# SCH.net
KiCad netlist of a schematic drawn in Altium Designer
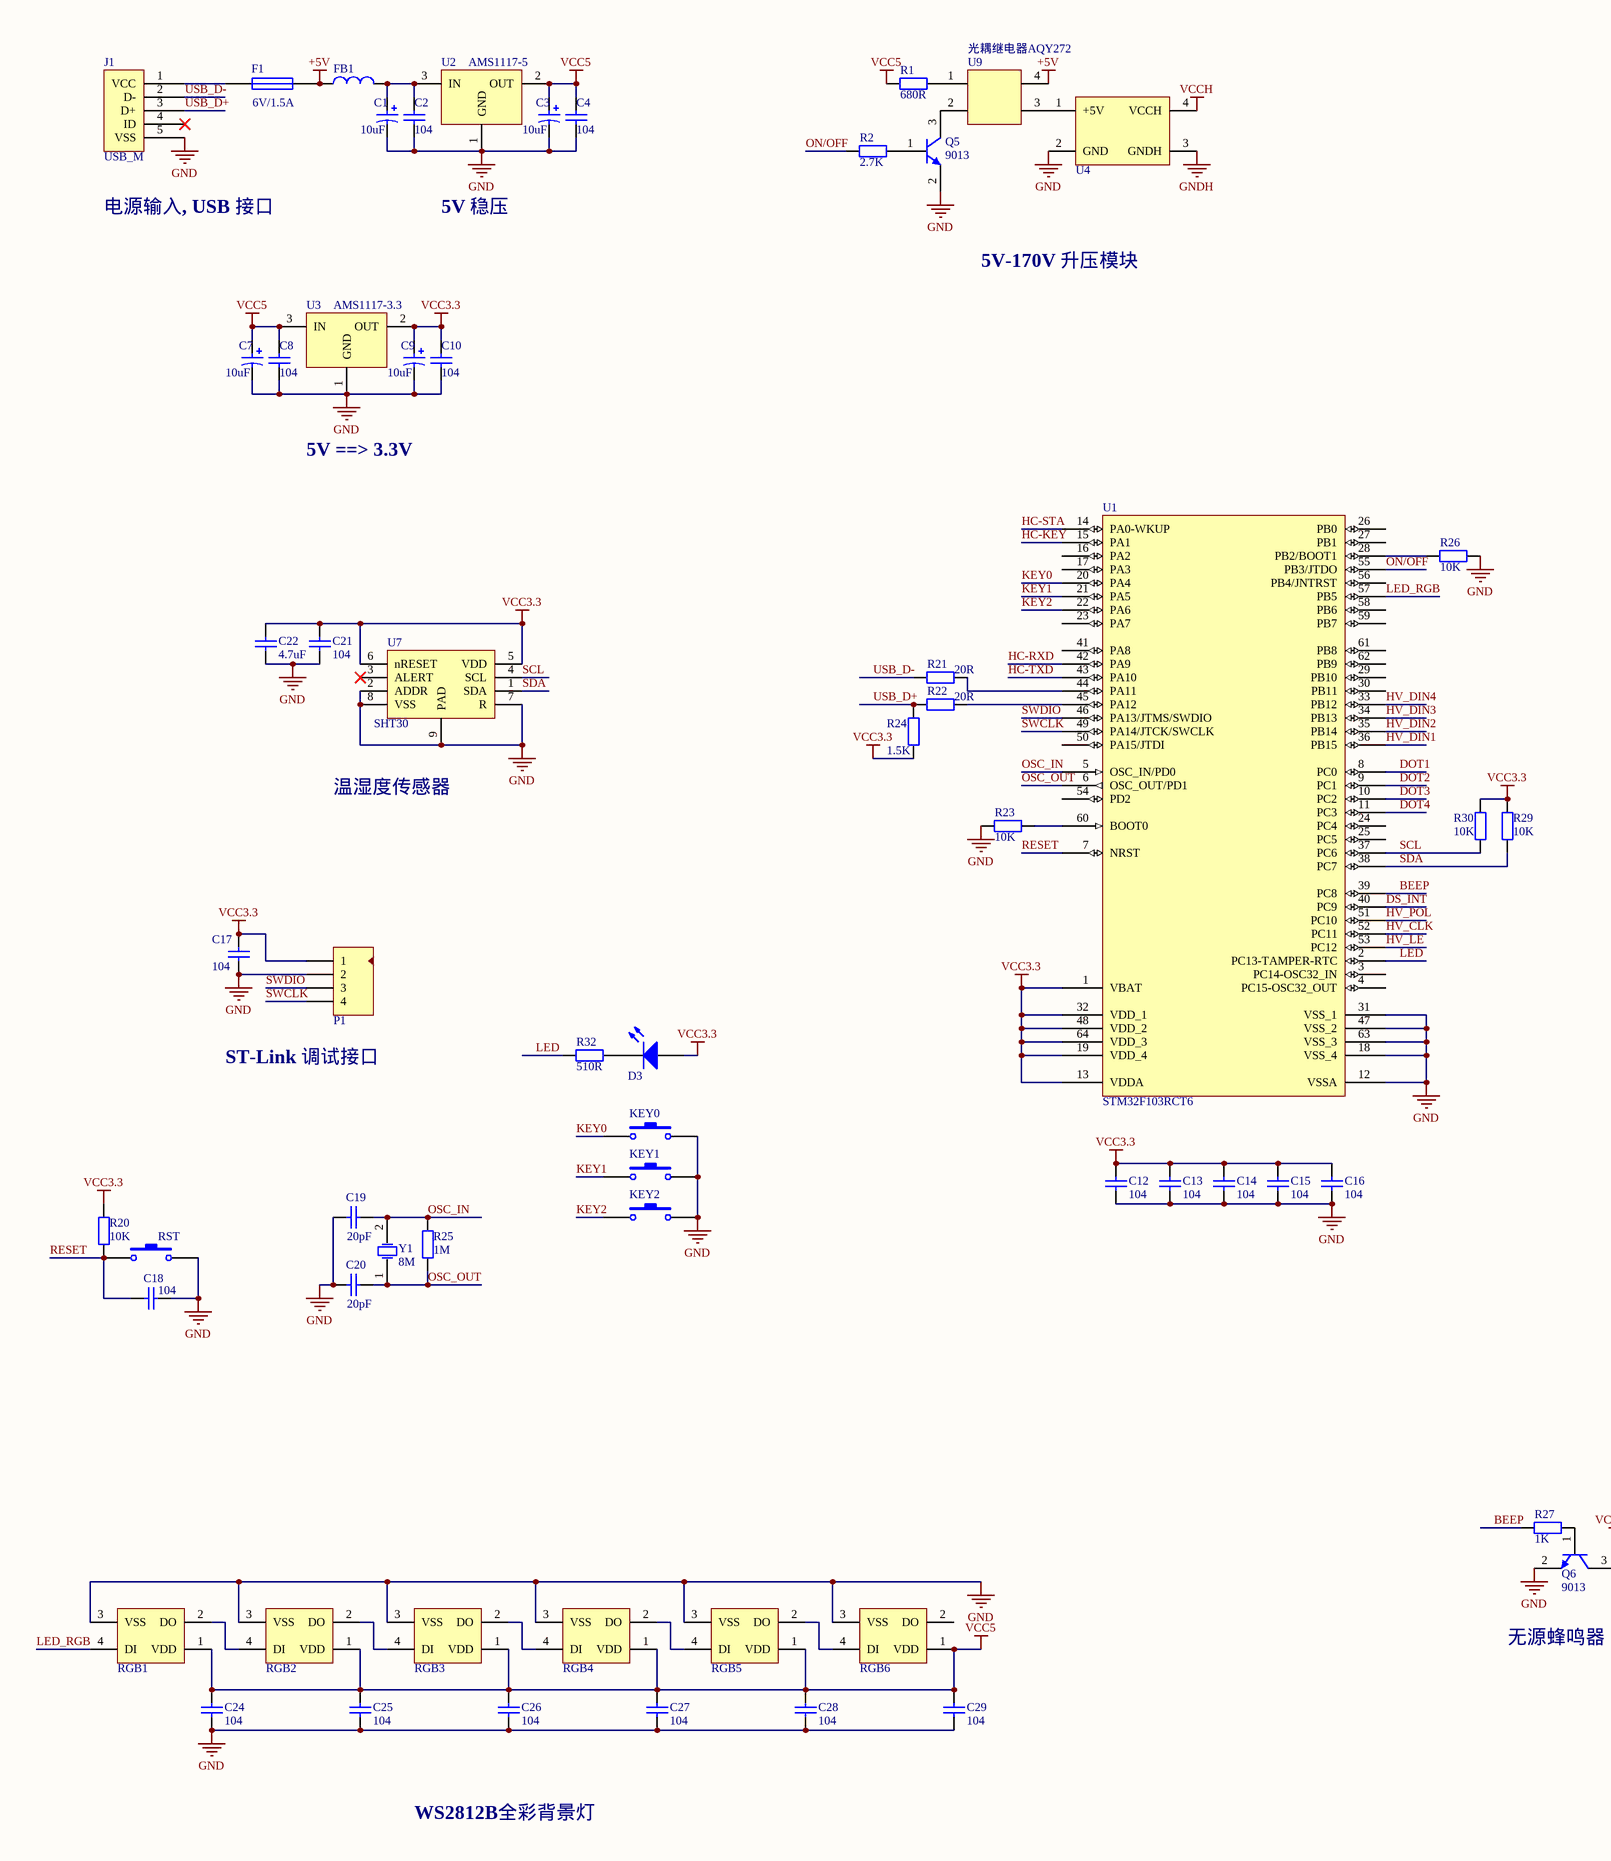
[diagram p0: SCH.SchDoc, left]
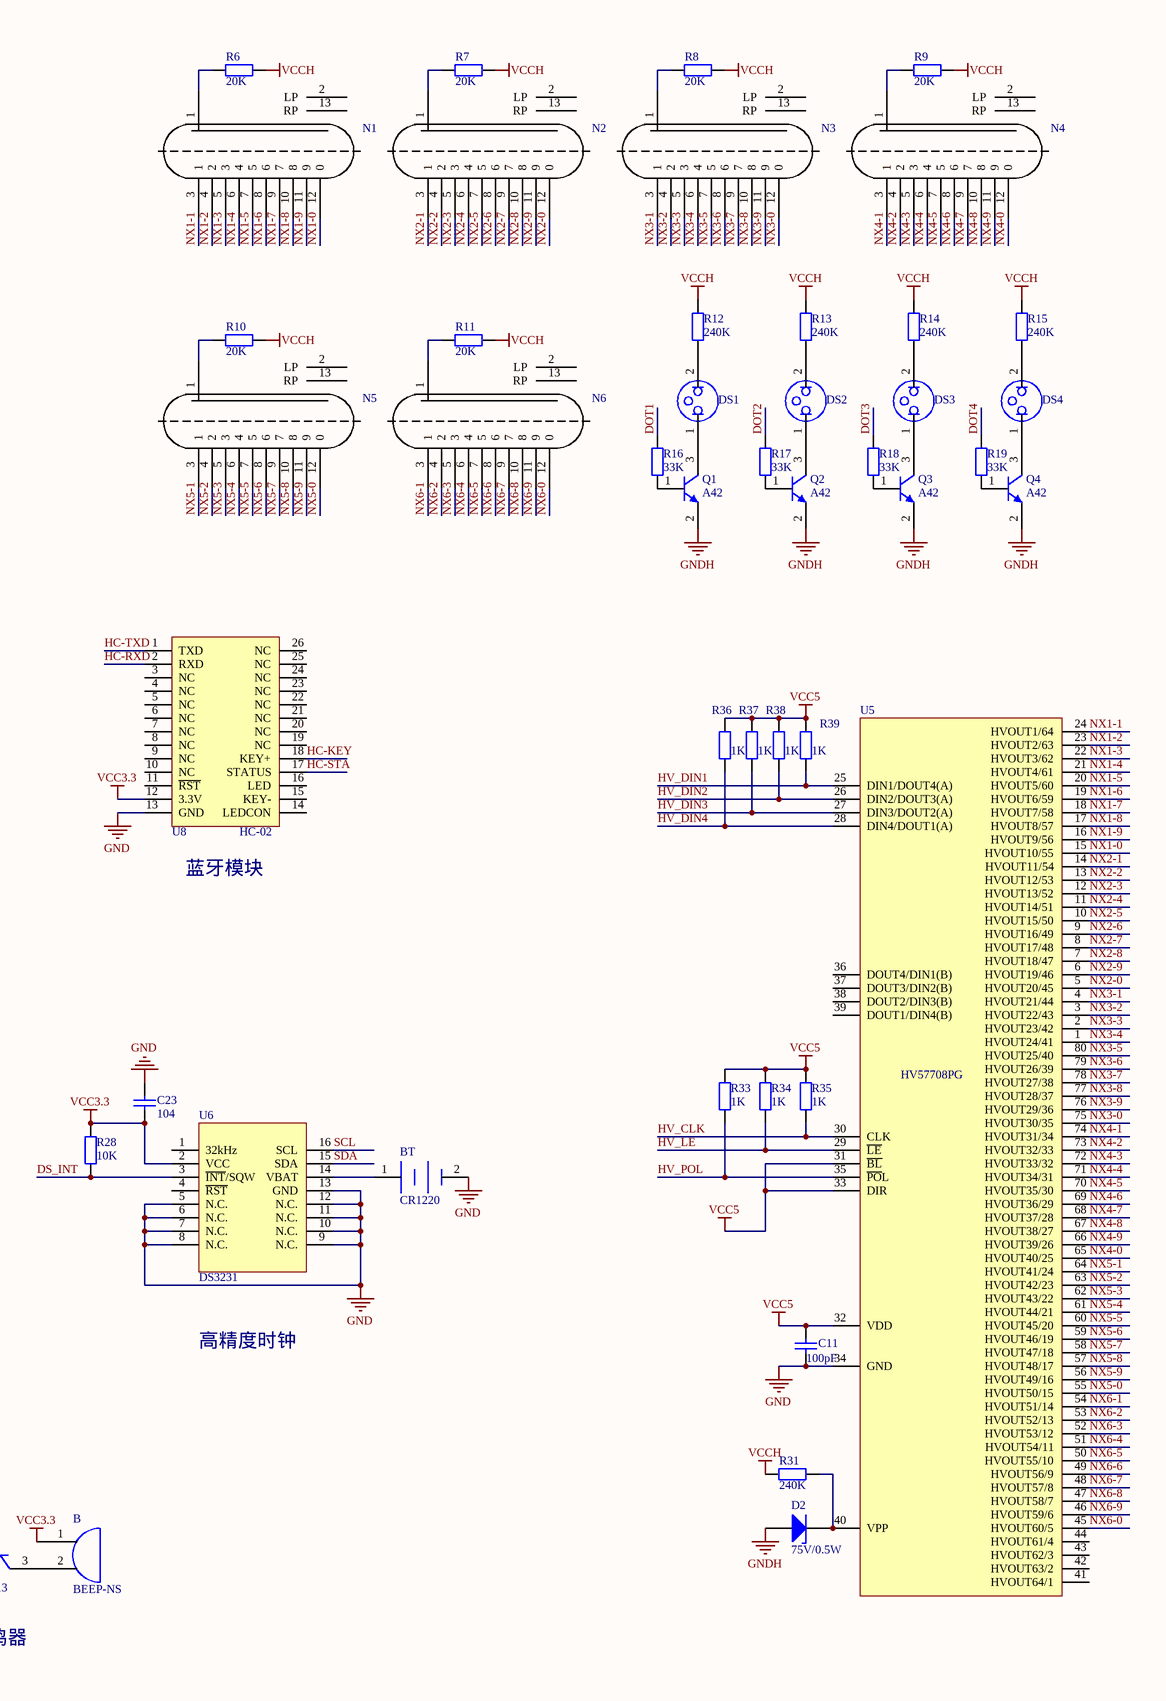
[diagram p1: SCH.SchDoc, right]

(export (version "E")
  (design (tool "Eeschema 10.0.6"))
  (components
    (comp (ref "B")
      (value "BEEP-NS")
      (footprint "BEEP-NS")
      (description "无源蜂鸣器")
      (libsource (lib "ChunLee") (part "BEEP-NS"))
    )
    (comp (ref "BT")
      (value "Battery")
      (footprint "CR1220")
      (fields (field (name "TYPE") "CR1220"))
      (libsource (lib "ChunLee") (part "Battery"))
    )
    (comp (ref "C1")
      (value "10uF")
      (footprint "C-1210")
      (description "钽电容")
      (fields (field (name "Comment") "Cap-Pol") (field (name "PUBLISHER") "Altium Limited"))
      (libsource (lib "ChunLee") (part "Cap-Pol-A"))
    )
    (comp (ref "C2")
      (value "104")
      (footprint "C-0805")
      (description "贴片瓷片电容")
      (fields (field (name "Comment") "Cap-S") (field (name "PUBLISHER") "Altium Limited"))
      (libsource (lib "ChunLee") (part "Cap-S"))
    )
    (comp (ref "C3")
      (value "10uF")
      (footprint "C-1210")
      (description "钽电容")
      (fields (field (name "Comment") "Cap-Pol") (field (name "PUBLISHER") "Altium Limited"))
      (libsource (lib "ChunLee") (part "Cap-Pol-A"))
    )
    (comp (ref "C4")
      (value "104")
      (footprint "C-0805")
      (description "贴片瓷片电容")
      (fields (field (name "Comment") "Cap-S") (field (name "PUBLISHER") "Altium Limited"))
      (libsource (lib "ChunLee") (part "Cap-S"))
    )
    (comp (ref "C7")
      (value "10uF")
      (footprint "C-1210")
      (description "钽电容")
      (fields (field (name "Comment") "Cap-Pol") (field (name "PUBLISHER") "Altium Limited"))
      (libsource (lib "ChunLee") (part "Cap-Pol-A"))
    )
    (comp (ref "C8")
      (value "104")
      (footprint "C-0805")
      (description "贴片瓷片电容")
      (fields (field (name "Comment") "Cap-S") (field (name "PUBLISHER") "Altium Limited"))
      (libsource (lib "ChunLee") (part "Cap-S"))
    )
    (comp (ref "C9")
      (value "10uF")
      (footprint "C-1210")
      (description "钽电容")
      (fields (field (name "Comment") "Cap-Pol") (field (name "PUBLISHER") "Altium Limited"))
      (libsource (lib "ChunLee") (part "Cap-Pol-A"))
    )
    (comp (ref "C10")
      (value "104")
      (footprint "C-0805")
      (description "贴片瓷片电容")
      (fields (field (name "Comment") "Cap-S") (field (name "PUBLISHER") "Altium Limited"))
      (libsource (lib "ChunLee") (part "Cap-S"))
    )
    (comp (ref "C11")
      (value "100pF")
      (footprint "C-0805")
      (description "贴片瓷片电容")
      (fields (field (name "Comment") "Cap-S") (field (name "PUBLISHER") "Altium Limited"))
      (libsource (lib "ChunLee") (part "Cap-S"))
    )
    (comp (ref "C12")
      (value "104")
      (footprint "C-0805")
      (description "贴片瓷片电容")
      (fields (field (name "Comment") "Cap-S") (field (name "PUBLISHER") "Altium Limited"))
      (libsource (lib "ChunLee") (part "Cap-S"))
    )
    (comp (ref "C13")
      (value "104")
      (footprint "C-0805")
      (description "贴片瓷片电容")
      (fields (field (name "Comment") "Cap-S") (field (name "PUBLISHER") "Altium Limited"))
      (libsource (lib "ChunLee") (part "Cap-S"))
    )
    (comp (ref "C14")
      (value "104")
      (footprint "C-0805")
      (description "贴片瓷片电容")
      (fields (field (name "Comment") "Cap-S") (field (name "PUBLISHER") "Altium Limited"))
      (libsource (lib "ChunLee") (part "Cap-S"))
    )
    (comp (ref "C15")
      (value "104")
      (footprint "C-0805")
      (description "贴片瓷片电容")
      (fields (field (name "Comment") "Cap-S") (field (name "PUBLISHER") "Altium Limited"))
      (libsource (lib "ChunLee") (part "Cap-S"))
    )
    (comp (ref "C16")
      (value "104")
      (footprint "C-0805")
      (description "贴片瓷片电容")
      (fields (field (name "Comment") "Cap-S") (field (name "PUBLISHER") "Altium Limited"))
      (libsource (lib "ChunLee") (part "Cap-S"))
    )
    (comp (ref "C17")
      (value "104")
      (footprint "C-0805")
      (description "贴片瓷片电容")
      (fields (field (name "Comment") "Cap-S") (field (name "PUBLISHER") "Altium Limited"))
      (libsource (lib "ChunLee") (part "Cap-S"))
    )
    (comp (ref "C18")
      (value "104")
      (footprint "C-0805")
      (description "贴片瓷片电容")
      (fields (field (name "Comment") "Cap-S") (field (name "PUBLISHER") "Altium Limited"))
      (libsource (lib "ChunLee") (part "Cap-S"))
    )
    (comp (ref "C19")
      (value "20pF")
      (footprint "C-0805")
      (description "贴片瓷片电容")
      (fields (field (name "Comment") "Cap-S") (field (name "PUBLISHER") "Altium Limited"))
      (libsource (lib "ChunLee") (part "Cap-S"))
    )
    (comp (ref "C20")
      (value "20pF")
      (footprint "C-0805")
      (description "贴片瓷片电容")
      (fields (field (name "Comment") "Cap-S") (field (name "PUBLISHER") "Altium Limited"))
      (libsource (lib "ChunLee") (part "Cap-S"))
    )
    (comp (ref "C21")
      (value "104")
      (footprint "C-0805")
      (description "贴片瓷片电容")
      (fields (field (name "Comment") "Cap-S") (field (name "PUBLISHER") "Altium Limited"))
      (libsource (lib "ChunLee") (part "Cap-S"))
    )
    (comp (ref "C22")
      (value "4.7uF")
      (footprint "C-0805")
      (description "贴片瓷片电容")
      (fields (field (name "Comment") "Cap-S") (field (name "PUBLISHER") "Altium Limited"))
      (libsource (lib "ChunLee") (part "Cap-S"))
    )
    (comp (ref "C23")
      (value "104")
      (footprint "C-0805")
      (description "贴片瓷片电容")
      (fields (field (name "Comment") "Cap-S") (field (name "PUBLISHER") "Altium Limited"))
      (libsource (lib "ChunLee") (part "Cap-S"))
    )
    (comp (ref "C24")
      (value "104")
      (footprint "C-0805")
      (description "贴片瓷片电容")
      (fields (field (name "Comment") "Cap-S") (field (name "PUBLISHER") "Altium Limited"))
      (libsource (lib "ChunLee") (part "Cap-S"))
    )
    (comp (ref "C25")
      (value "104")
      (footprint "C-0805")
      (description "贴片瓷片电容")
      (fields (field (name "Comment") "Cap-S") (field (name "PUBLISHER") "Altium Limited"))
      (libsource (lib "ChunLee") (part "Cap-S"))
    )
    (comp (ref "C26")
      (value "104")
      (footprint "C-0805")
      (description "贴片瓷片电容")
      (fields (field (name "Comment") "Cap-S") (field (name "PUBLISHER") "Altium Limited"))
      (libsource (lib "ChunLee") (part "Cap-S"))
    )
    (comp (ref "C27")
      (value "104")
      (footprint "C-0805")
      (description "贴片瓷片电容")
      (fields (field (name "Comment") "Cap-S") (field (name "PUBLISHER") "Altium Limited"))
      (libsource (lib "ChunLee") (part "Cap-S"))
    )
    (comp (ref "C28")
      (value "104")
      (footprint "C-0805")
      (description "贴片瓷片电容")
      (fields (field (name "Comment") "Cap-S") (field (name "PUBLISHER") "Altium Limited"))
      (libsource (lib "ChunLee") (part "Cap-S"))
    )
    (comp (ref "C29")
      (value "104")
      (footprint "C-0805")
      (description "贴片瓷片电容")
      (fields (field (name "Comment") "Cap-S") (field (name "PUBLISHER") "Altium Limited"))
      (libsource (lib "ChunLee") (part "Cap-S"))
    )
    (comp (ref "D2")
      (value "75V/0.5W")
      (footprint "D-ll34")
      (description "稳压二极管")
      (fields (field (name "Comment") "ZMM75") (field (name "PUBLISHER") "Altium Limited"))
      (libsource (lib "ChunLee") (part "Diode-Z"))
    )
    (comp (ref "D3")
      (value "LED0")
      (footprint "LED-0805")
      (description "发光二极管")
      (fields (field (name "PUBLISHER") "Altium Limited"))
      (libsource (lib "ChunLee") (part "LED0"))
    )
    (comp (ref "DS1")
      (value "Neon")
      (footprint "PIN2")
      (description "氖泡")
      (libsource (lib "ChunLee") (part "Neon_Lamp"))
    )
    (comp (ref "DS2")
      (value "Neon")
      (footprint "PIN2")
      (description "氖泡")
      (libsource (lib "ChunLee") (part "Neon_Lamp"))
    )
    (comp (ref "DS3")
      (value "Neon")
      (footprint "PIN2")
      (description "氖泡")
      (libsource (lib "ChunLee") (part "Neon_Lamp"))
    )
    (comp (ref "DS4")
      (value "Neon")
      (footprint "PIN2")
      (description "氖泡")
      (libsource (lib "ChunLee") (part "Neon_Lamp"))
    )
    (comp (ref "F1")
      (value "6V/1.5A")
      (footprint "1206")
      (description "保险丝")
      (fields (field (name "Comment") "Fuse1"))
      (libsource (lib "ChunLee") (part "Fuse1"))
    )
    (comp (ref "FB1")
      (value "Inductor")
      (footprint "0805-1")
      (description "磁珠")
      (fields (field (name "PUBLISHER") "Altium Limited"))
      (libsource (lib "ChunLee") (part "Inductor"))
    )
    (comp (ref "J1")
      (value "USB_M")
      (footprint "USB_MICRO")
      (description "Micro/Mini USB")
      (libsource (lib "HDR_ChunLee") (part "USB_M"))
    )
    (comp (ref "KEY0")
      (value "KEY")
      (footprint "SW_PB2_C1")
      (description "微动开关")
      (fields (field (name "PUBLISHER") "Altium Limited"))
      (libsource (lib "ChunLee") (part "SW-PB"))
    )
    (comp (ref "KEY1")
      (value "KEY")
      (footprint "SW_PB2_C1")
      (description "微动开关")
      (fields (field (name "PUBLISHER") "Altium Limited"))
      (libsource (lib "ChunLee") (part "SW-PB"))
    )
    (comp (ref "KEY2")
      (value "KEY")
      (footprint "SW_PB2_C1")
      (description "微动开关")
      (fields (field (name "PUBLISHER") "Altium Limited"))
      (libsource (lib "ChunLee") (part "SW-PB"))
    )
    (comp (ref "N1")
      (value "IN_14")
      (footprint "IN_14")
      (description "辉光管")
      (libsource (lib "ChunLee") (part "IN_14"))
    )
    (comp (ref "N2")
      (value "IN_14")
      (footprint "IN_14")
      (description "辉光管")
      (libsource (lib "ChunLee") (part "IN_14"))
    )
    (comp (ref "N3")
      (value "IN_14")
      (footprint "IN_14")
      (description "辉光管")
      (libsource (lib "ChunLee") (part "IN_14"))
    )
    (comp (ref "N4")
      (value "IN_14")
      (footprint "IN_14")
      (description "辉光管")
      (libsource (lib "ChunLee") (part "IN_14"))
    )
    (comp (ref "N5")
      (value "IN_14")
      (footprint "IN_14")
      (description "辉光管")
      (libsource (lib "ChunLee") (part "IN_14"))
    )
    (comp (ref "N6")
      (value "IN_14")
      (footprint "IN_14")
      (description "辉光管")
      (libsource (lib "ChunLee") (part "IN_14"))
    )
    (comp (ref "P1")
      (value "Header 4")
      (footprint "HDR4X1-2.54")
      (description "接插件")
      (fields (field (name "PUBLISHER") "Altium Limited"))
      (libsource (lib "HDR_ChunLee") (part "Header 4"))
    )
    (comp (ref "Q1")
      (value "A42")
      (footprint "SOT23-3")
      (description "贴片三极管")
      (fields (field (name "PUBLISHER") "Altium Limited"))
      (libsource (lib "ChunLee") (part "NPN1"))
    )
    (comp (ref "Q2")
      (value "A42")
      (footprint "SOT23-3")
      (description "贴片三极管")
      (fields (field (name "PUBLISHER") "Altium Limited"))
      (libsource (lib "ChunLee") (part "NPN1"))
    )
    (comp (ref "Q3")
      (value "A42")
      (footprint "SOT23-3")
      (description "贴片三极管")
      (fields (field (name "PUBLISHER") "Altium Limited"))
      (libsource (lib "ChunLee") (part "NPN1"))
    )
    (comp (ref "Q4")
      (value "A42")
      (footprint "SOT23-3")
      (description "贴片三极管")
      (fields (field (name "PUBLISHER") "Altium Limited"))
      (libsource (lib "ChunLee") (part "NPN1"))
    )
    (comp (ref "Q5")
      (value "9013")
      (footprint "SOT23-3")
      (description "贴片三极管")
      (fields (field (name "PUBLISHER") "Altium Limited"))
      (libsource (lib "ChunLee") (part "NPN1"))
    )
    (comp (ref "Q6")
      (value "9013")
      (footprint "SOT23-3")
      (description "贴片三极管")
      (fields (field (name "PUBLISHER") "Altium Limited"))
      (libsource (lib "ChunLee") (part "NPN1"))
    )
    (comp (ref "R1")
      (value "680R")
      (footprint "0805-1")
      (description "贴片电阻")
      (fields (field (name "Comment") "Res1") (field (name "PUBLISHER") "Altium Limited"))
      (libsource (lib "") (part "Res1_2"))
    )
    (comp (ref "R2")
      (value "2.7K")
      (footprint "0805-1")
      (description "贴片电阻")
      (fields (field (name "Comment") "Res1") (field (name "PUBLISHER") "Altium Limited"))
      (libsource (lib "") (part "Res1_3"))
    )
    (comp (ref "R6")
      (value "20K")
      (footprint "0805-1")
      (description "贴片电阻")
      (fields (field (name "Comment") "Res1") (field (name "PUBLISHER") "Altium Limited"))
      (libsource (lib "") (part "Res1_2"))
    )
    (comp (ref "R7")
      (value "20K")
      (footprint "0805-1")
      (description "贴片电阻")
      (fields (field (name "Comment") "Res1") (field (name "PUBLISHER") "Altium Limited"))
      (libsource (lib "") (part "Res1_2"))
    )
    (comp (ref "R8")
      (value "20K")
      (footprint "0805-1")
      (description "贴片电阻")
      (fields (field (name "Comment") "Res1") (field (name "PUBLISHER") "Altium Limited"))
      (libsource (lib "") (part "Res1_2"))
    )
    (comp (ref "R9")
      (value "20K")
      (footprint "0805-1")
      (description "贴片电阻")
      (fields (field (name "Comment") "Res1") (field (name "PUBLISHER") "Altium Limited"))
      (libsource (lib "") (part "Res1_2"))
    )
    (comp (ref "R10")
      (value "20K")
      (footprint "0805-1")
      (description "贴片电阻")
      (fields (field (name "Comment") "Res1") (field (name "PUBLISHER") "Altium Limited"))
      (libsource (lib "") (part "Res1_2"))
    )
    (comp (ref "R11")
      (value "20K")
      (footprint "0805-1")
      (description "贴片电阻")
      (fields (field (name "Comment") "Res1") (field (name "PUBLISHER") "Altium Limited"))
      (libsource (lib "") (part "Res1_2"))
    )
    (comp (ref "R12")
      (value "240K")
      (footprint "0805-1")
      (description "贴片电阻")
      (fields (field (name "Comment") "Res1") (field (name "PUBLISHER") "Altium Limited"))
      (libsource (lib "ChunLee") (part "Res1"))
    )
    (comp (ref "R13")
      (value "240K")
      (footprint "0805-1")
      (description "贴片电阻")
      (fields (field (name "Comment") "Res1") (field (name "PUBLISHER") "Altium Limited"))
      (libsource (lib "ChunLee") (part "Res1"))
    )
    (comp (ref "R14")
      (value "240K")
      (footprint "0805-1")
      (description "贴片电阻")
      (fields (field (name "Comment") "Res1") (field (name "PUBLISHER") "Altium Limited"))
      (libsource (lib "") (part "Res1_1"))
    )
    (comp (ref "R15")
      (value "240K")
      (footprint "0805-1")
      (description "贴片电阻")
      (fields (field (name "Comment") "Res1") (field (name "PUBLISHER") "Altium Limited"))
      (libsource (lib "ChunLee") (part "Res1"))
    )
    (comp (ref "R16")
      (value "33K")
      (footprint "0805-1")
      (description "贴片电阻")
      (fields (field (name "Comment") "Res1") (field (name "PUBLISHER") "Altium Limited"))
      (libsource (lib "ChunLee") (part "Res1"))
    )
    (comp (ref "R17")
      (value "33K")
      (footprint "0805-1")
      (description "贴片电阻")
      (fields (field (name "Comment") "Res1") (field (name "PUBLISHER") "Altium Limited"))
      (libsource (lib "ChunLee") (part "Res1"))
    )
    (comp (ref "R18")
      (value "33K")
      (footprint "0805-1")
      (description "贴片电阻")
      (fields (field (name "Comment") "Res1") (field (name "PUBLISHER") "Altium Limited"))
      (libsource (lib "ChunLee") (part "Res1"))
    )
    (comp (ref "R19")
      (value "33K")
      (footprint "0805-1")
      (description "贴片电阻")
      (fields (field (name "Comment") "Res1") (field (name "PUBLISHER") "Altium Limited"))
      (libsource (lib "ChunLee") (part "Res1"))
    )
    (comp (ref "R20")
      (value "10K")
      (footprint "0805-1")
      (description "贴片电阻")
      (fields (field (name "Comment") "Res1") (field (name "PUBLISHER") "Altium Limited"))
      (libsource (lib "") (part "Res1_1"))
    )
    (comp (ref "R21")
      (value "20R")
      (footprint "0805-1")
      (description "贴片电阻")
      (fields (field (name "Comment") "Res1") (field (name "PUBLISHER") "Altium Limited"))
      (libsource (lib "") (part "Res1_2"))
    )
    (comp (ref "R22")
      (value "20R")
      (footprint "0805-1")
      (description "贴片电阻")
      (fields (field (name "Comment") "Res1") (field (name "PUBLISHER") "Altium Limited"))
      (libsource (lib "") (part "Res1_2"))
    )
    (comp (ref "R23")
      (value "10K")
      (footprint "0805-1")
      (description "贴片电阻")
      (fields (field (name "Comment") "Res1") (field (name "PUBLISHER") "Altium Limited"))
      (libsource (lib "") (part "Res1_2"))
    )
    (comp (ref "R24")
      (value "1.5K")
      (footprint "0805-1")
      (description "贴片电阻")
      (fields (field (name "Comment") "Res1") (field (name "PUBLISHER") "Altium Limited"))
      (libsource (lib "ChunLee") (part "Res1"))
    )
    (comp (ref "R25")
      (value "1M")
      (footprint "0805-1")
      (description "贴片电阻")
      (fields (field (name "Comment") "Res1") (field (name "PUBLISHER") "Altium Limited"))
      (libsource (lib "") (part "Res1_1"))
    )
    (comp (ref "R26")
      (value "10K")
      (footprint "0805-1")
      (description "贴片电阻")
      (fields (field (name "Comment") "Res1") (field (name "PUBLISHER") "Altium Limited"))
      (libsource (lib "") (part "Res1_2"))
    )
    (comp (ref "R27")
      (value "1K")
      (footprint "0805-1")
      (description "贴片电阻")
      (fields (field (name "Comment") "Res1") (field (name "PUBLISHER") "Altium Limited"))
      (libsource (lib "") (part "Res1_2"))
    )
    (comp (ref "R28")
      (value "10K")
      (footprint "0805-1")
      (description "贴片电阻")
      (fields (field (name "Comment") "Res1") (field (name "PUBLISHER") "Altium Limited"))
      (libsource (lib "") (part "Res1_1"))
    )
    (comp (ref "R29")
      (value "10K")
      (footprint "0805-1")
      (description "贴片电阻")
      (fields (field (name "Comment") "Res1") (field (name "PUBLISHER") "Altium Limited"))
      (libsource (lib "") (part "Res1_1"))
    )
    (comp (ref "R30")
      (value "10K")
      (footprint "0805-1")
      (description "贴片电阻")
      (fields (field (name "Comment") "Res1") (field (name "PUBLISHER") "Altium Limited"))
      (libsource (lib "") (part "Res1_1"))
    )
    (comp (ref "R31")
      (value "240K")
      (footprint "0805-1")
      (description "贴片电阻")
      (fields (field (name "Comment") "Res1") (field (name "PUBLISHER") "Altium Limited"))
      (libsource (lib "") (part "Res1_2"))
    )
    (comp (ref "R32")
      (value "510R")
      (footprint "0805-1")
      (description "贴片电阻")
      (fields (field (name "Comment") "Res1") (field (name "PUBLISHER") "Altium Limited"))
      (libsource (lib "") (part "Res1_2"))
    )
    (comp (ref "R33")
      (value "1K")
      (footprint "0805-1")
      (description "贴片电阻")
      (fields (field (name "Comment") "Res1") (field (name "PUBLISHER") "Altium Limited"))
      (libsource (lib "") (part "Res1_1"))
    )
    (comp (ref "R34")
      (value "1K")
      (footprint "0805-1")
      (description "贴片电阻")
      (fields (field (name "Comment") "Res1") (field (name "PUBLISHER") "Altium Limited"))
      (libsource (lib "") (part "Res1_1"))
    )
    (comp (ref "R35")
      (value "1K")
      (footprint "0805-1")
      (description "贴片电阻")
      (fields (field (name "Comment") "Res1") (field (name "PUBLISHER") "Altium Limited"))
      (libsource (lib "") (part "Res1_1"))
    )
    (comp (ref "R36")
      (value "1K")
      (footprint "0805-1")
      (description "贴片电阻")
      (fields (field (name "Comment") "Res1") (field (name "PUBLISHER") "Altium Limited"))
      (libsource (lib "") (part "Res1_1"))
    )
    (comp (ref "R37")
      (value "1K")
      (footprint "0805-1")
      (description "贴片电阻")
      (fields (field (name "Comment") "Res1") (field (name "PUBLISHER") "Altium Limited"))
      (libsource (lib "") (part "Res1_1"))
    )
    (comp (ref "R38")
      (value "1K")
      (footprint "0805-1")
      (description "贴片电阻")
      (fields (field (name "Comment") "Res1") (field (name "PUBLISHER") "Altium Limited"))
      (libsource (lib "") (part "Res1_1"))
    )
    (comp (ref "R39")
      (value "1K")
      (footprint "0805-1")
      (description "贴片电阻")
      (fields (field (name "Comment") "Res1") (field (name "PUBLISHER") "Altium Limited"))
      (libsource (lib "") (part "Res1_1"))
    )
    (comp (ref "RGB1")
      (value "WS2812B")
      (footprint "SMD-5050-4")
      (description "WS2812B 4脚RGB全彩LED")
      (libsource (lib "ChunLee") (part "WS2812B"))
    )
    (comp (ref "RGB2")
      (value "WS2812B")
      (footprint "SMD-5050-4")
      (description "WS2812B 4脚RGB全彩LED")
      (libsource (lib "ChunLee") (part "WS2812B"))
    )
    (comp (ref "RGB3")
      (value "WS2812B")
      (footprint "SMD-5050-4")
      (description "WS2812B 4脚RGB全彩LED")
      (libsource (lib "ChunLee") (part "WS2812B"))
    )
    (comp (ref "RGB4")
      (value "WS2812B")
      (footprint "SMD-5050-4")
      (description "WS2812B 4脚RGB全彩LED")
      (libsource (lib "ChunLee") (part "WS2812B"))
    )
    (comp (ref "RGB5")
      (value "WS2812B")
      (footprint "SMD-5050-4")
      (description "WS2812B 4脚RGB全彩LED")
      (libsource (lib "ChunLee") (part "WS2812B"))
    )
    (comp (ref "RGB6")
      (value "WS2812B")
      (footprint "SMD-5050-4")
      (description "WS2812B 4脚RGB全彩LED")
      (libsource (lib "ChunLee") (part "WS2812B"))
    )
    (comp (ref "RST")
      (value "SW-PB")
      (footprint "SW_PB2_A1")
      (description "微动开关")
      (fields (field (name "PUBLISHER") "Altium Limited"))
      (libsource (lib "ChunLee") (part "SW-PB"))
    )
    (comp (ref "U1")
      (value "STM32F103RCT6")
      (footprint "LQFP-64")
      (description "STM32F103, 64引脚, 256Kb Flash, 48Kb SRAM")
      (fields (field (name "PUBLISHER") "Altium Limited"))
      (libsource (lib "ChunLee") (part "STM32F103RCT6"))
    )
    (comp (ref "U2")
      (value "AMS1117-5")
      (footprint "SOT223")
      (description "5V稳压芯片")
      (libsource (lib "ChunLee") (part "AMS1117"))
    )
    (comp (ref "U3")
      (value "AMS1117-3.3")
      (footprint "SOT223")
      (description "3.3V稳压芯片")
      (libsource (lib "ChunLee") (part "AMS1117"))
    )
    (comp (ref "U4")
      (value "Boost")
      (footprint "BOOST-A")
      (description "5V-->170V")
      (libsource (lib "Nixie_Schlib") (part "升压模块5V-170V"))
    )
    (comp (ref "U5")
      (value "HV57708PG")
      (footprint "PQFP-80")
      (description "32MHz, 64通道推挽输出串入并出芯片")
      (libsource (lib "ChunLee") (part "HV57708PG"))
    )
    (comp (ref "U6")
      (value "DS3231")
      (footprint "SOIC-16W")
      (description "高精度时钟芯片")
      (libsource (lib "ChunLee") (part "DS3231"))
    )
    (comp (ref "U7")
      (value "SHT30")
      (footprint "SHT3x-DIS")
      (description "温湿度传感器")
      (libsource (lib "ChunLee") (part "SHT3X"))
    )
    (comp (ref "U8")
      (value "HC-02")
      (footprint "HC-02")
      (description "串口蓝牙4.0, 10m")
      (libsource (lib "ChunLee") (part "HC-02"))
    )
    (comp (ref "U9")
      (value "光耦继电器AQY272")
      (footprint "AQY272-SOP")
      (description "继电器")
      (libsource (lib "ChunLee") (part "RELAY-AQY272"))
    )
    (comp (ref "Y1")
      (value "8M")
      (footprint "X-SM49")
      (description "晶振")
      (fields (field (name "Comment") "XTAL") (field (name "PUBLISHER") "Altium Limited"))
      (libsource (lib "ChunLee") (part "XTAL"))
    )
  )
  (nets
    (net (code "1") (name "+5V") (class "Default")
      (node (ref "F1") (pin "2") (pinfunction "2_2") (pintype "passive"))
      (node (ref "FB1") (pin "1") (pinfunction "1_1") (pintype "passive"))
      (node (ref "U9") (pin "4") (pinfunction "4_4") (pintype "passive"))
    )
    (net (code "2") (name "/BEEP") (class "Default")
      (node (ref "R27") (pin "1") (pinfunction "1_1") (pintype "passive"))
      (node (ref "U1") (pin "39") (pinfunction "PC8_39") (pintype "bidirectional"))
    )
    (net (code "3") (name "/DOT1") (class "Default")
      (node (ref "R16") (pin "1") (pinfunction "1_1") (pintype "passive"))
      (node (ref "U1") (pin "8") (pinfunction "PC0_8") (pintype "bidirectional"))
    )
    (net (code "4") (name "/DOT2") (class "Default")
      (node (ref "R17") (pin "1") (pinfunction "1_1") (pintype "passive"))
      (node (ref "U1") (pin "9") (pinfunction "PC1_9") (pintype "bidirectional"))
    )
    (net (code "5") (name "/DOT3") (class "Default")
      (node (ref "R18") (pin "1") (pinfunction "1_1") (pintype "passive"))
      (node (ref "U1") (pin "10") (pinfunction "PC2_10") (pintype "bidirectional"))
    )
    (net (code "6") (name "/DOT4") (class "Default")
      (node (ref "R19") (pin "1") (pinfunction "1_1") (pintype "passive"))
      (node (ref "U1") (pin "11") (pinfunction "PC3_11") (pintype "bidirectional"))
    )
    (net (code "7") (name "/DS_INT") (class "Default")
      (node (ref "R28") (pin "1") (pinfunction "1_1") (pintype "passive"))
      (node (ref "U1") (pin "40") (pinfunction "PC9_40") (pintype "bidirectional"))
      (node (ref "U6") (pin "3") (pinfunction "~{INT}/SQW_3") (pintype "passive"))
    )
    (net (code "8") (name "/HC-KEY") (class "Default")
      (node (ref "U1") (pin "15") (pinfunction "PA1_15") (pintype "bidirectional"))
      (node (ref "U8") (pin "18") (pinfunction "KEY+_18") (pintype "passive"))
    )
    (net (code "9") (name "/HC-RXD") (class "Default")
      (node (ref "U1") (pin "42") (pinfunction "PA9_42") (pintype "bidirectional"))
      (node (ref "U8") (pin "2") (pinfunction "RXD_2") (pintype "passive"))
    )
    (net (code "10") (name "/HC-STA") (class "Default")
      (node (ref "U1") (pin "14") (pinfunction "PA0-WKUP_14") (pintype "bidirectional"))
      (node (ref "U8") (pin "17") (pinfunction "STATUS_17") (pintype "passive"))
    )
    (net (code "11") (name "/HC-TXD") (class "Default")
      (node (ref "U1") (pin "43") (pinfunction "PA10_43") (pintype "bidirectional"))
      (node (ref "U8") (pin "1") (pinfunction "TXD_1") (pintype "passive"))
    )
    (net (code "12") (name "/HV_CLK") (class "Default")
      (node (ref "R35") (pin "1") (pinfunction "1_1") (pintype "passive"))
      (node (ref "U1") (pin "52") (pinfunction "PC11_52") (pintype "bidirectional"))
      (node (ref "U5") (pin "30") (pinfunction "CLK_30") (pintype "passive"))
    )
    (net (code "13") (name "/HV_DIN1") (class "Default")
      (node (ref "R39") (pin "1") (pinfunction "1_1") (pintype "passive"))
      (node (ref "U1") (pin "36") (pinfunction "PB15_36") (pintype "bidirectional"))
      (node (ref "U5") (pin "25") (pinfunction "DIN1/DOUT4(A)_25") (pintype "passive"))
    )
    (net (code "14") (name "/HV_DIN2") (class "Default")
      (node (ref "R38") (pin "1") (pinfunction "1_1") (pintype "passive"))
      (node (ref "U1") (pin "35") (pinfunction "PB14_35") (pintype "bidirectional"))
      (node (ref "U5") (pin "26") (pinfunction "DIN2/DOUT3(A)_26") (pintype "passive"))
    )
    (net (code "15") (name "/HV_DIN3") (class "Default")
      (node (ref "R37") (pin "1") (pinfunction "1_1") (pintype "passive"))
      (node (ref "U1") (pin "34") (pinfunction "PB13_34") (pintype "bidirectional"))
      (node (ref "U5") (pin "27") (pinfunction "DIN3/DOUT2(A)_27") (pintype "passive"))
    )
    (net (code "16") (name "/HV_DIN4") (class "Default")
      (node (ref "R36") (pin "1") (pinfunction "1_1") (pintype "passive"))
      (node (ref "U1") (pin "33") (pinfunction "PB12_33") (pintype "bidirectional"))
      (node (ref "U5") (pin "28") (pinfunction "DIN4/DOUT1(A)_28") (pintype "passive"))
    )
    (net (code "17") (name "/HV_LE") (class "Default")
      (node (ref "R34") (pin "1") (pinfunction "1_1") (pintype "passive"))
      (node (ref "U1") (pin "53") (pinfunction "PC12_53") (pintype "bidirectional"))
      (node (ref "U5") (pin "29") (pinfunction "~{LE}_29") (pintype "passive"))
    )
    (net (code "18") (name "/HV_POL") (class "Default")
      (node (ref "R33") (pin "1") (pinfunction "1_1") (pintype "passive"))
      (node (ref "U1") (pin "51") (pinfunction "PC10_51") (pintype "bidirectional"))
      (node (ref "U5") (pin "35") (pinfunction "~{PO}L_35") (pintype "passive"))
    )
    (net (code "19") (name "/KEY0") (class "Default")
      (node (ref "KEY0") (pin "1") (pinfunction "1_1") (pintype "passive"))
      (node (ref "U1") (pin "20") (pinfunction "PA4_20") (pintype "bidirectional"))
    )
    (net (code "20") (name "/KEY1") (class "Default")
      (node (ref "KEY1") (pin "1") (pinfunction "1_1") (pintype "passive"))
      (node (ref "U1") (pin "21") (pinfunction "PA5_21") (pintype "bidirectional"))
    )
    (net (code "21") (name "/KEY2") (class "Default")
      (node (ref "KEY2") (pin "1") (pinfunction "1_1") (pintype "passive"))
      (node (ref "U1") (pin "22") (pinfunction "PA6_22") (pintype "bidirectional"))
    )
    (net (code "22") (name "/LED") (class "Default")
      (node (ref "R32") (pin "1") (pinfunction "1_1") (pintype "passive"))
      (node (ref "U1") (pin "2") (pinfunction "PC13-TAMPER-RTC_2") (pintype "bidirectional"))
    )
    (net (code "23") (name "/LED_RGB") (class "Default")
      (node (ref "RGB1") (pin "4") (pinfunction "DI_4") (pintype "passive"))
      (node (ref "U1") (pin "57") (pinfunction "PB5_57") (pintype "bidirectional"))
    )
    (net (code "24") (name "/NX1-0") (class "Default")
      (node (ref "N1") (pin "12") (pinfunction "0_12") (pintype "passive"))
      (node (ref "U5") (pin "15") (pinfunction "HVOUT10/55_15") (pintype "passive"))
    )
    (net (code "25") (name "/NX1-1") (class "Default")
      (node (ref "N1") (pin "3") (pinfunction "1_3") (pintype "passive"))
      (node (ref "U5") (pin "24") (pinfunction "HVOUT1/64_24") (pintype "passive"))
    )
    (net (code "26") (name "/NX1-2") (class "Default")
      (node (ref "N1") (pin "4") (pinfunction "2_4") (pintype "passive"))
      (node (ref "U5") (pin "23") (pinfunction "HVOUT2/63_23") (pintype "passive"))
    )
    (net (code "27") (name "/NX1-3") (class "Default")
      (node (ref "N1") (pin "5") (pinfunction "3_5") (pintype "passive"))
      (node (ref "U5") (pin "22") (pinfunction "HVOUT3/62_22") (pintype "passive"))
    )
    (net (code "28") (name "/NX1-4") (class "Default")
      (node (ref "N1") (pin "6") (pinfunction "4_6") (pintype "passive"))
      (node (ref "U5") (pin "21") (pinfunction "HVOUT4/61_21") (pintype "passive"))
    )
    (net (code "29") (name "/NX1-5") (class "Default")
      (node (ref "N1") (pin "7") (pinfunction "5_7") (pintype "passive"))
      (node (ref "U5") (pin "20") (pinfunction "HVOUT5/60_20") (pintype "passive"))
    )
    (net (code "30") (name "/NX1-6") (class "Default")
      (node (ref "N1") (pin "8") (pinfunction "6_8") (pintype "passive"))
      (node (ref "U5") (pin "19") (pinfunction "HVOUT6/59_19") (pintype "passive"))
    )
    (net (code "31") (name "/NX1-7") (class "Default")
      (node (ref "N1") (pin "9") (pinfunction "7_9") (pintype "passive"))
      (node (ref "U5") (pin "18") (pinfunction "HVOUT7/58_18") (pintype "passive"))
    )
    (net (code "32") (name "/NX1-8") (class "Default")
      (node (ref "N1") (pin "10") (pinfunction "8_10") (pintype "passive"))
      (node (ref "U5") (pin "17") (pinfunction "HVOUT8/57_17") (pintype "passive"))
    )
    (net (code "33") (name "/NX1-9") (class "Default")
      (node (ref "N1") (pin "11") (pinfunction "9_11") (pintype "passive"))
      (node (ref "U5") (pin "16") (pinfunction "HVOUT9/56_16") (pintype "passive"))
    )
    (net (code "34") (name "/NX2-0") (class "Default")
      (node (ref "N2") (pin "12") (pinfunction "0_12") (pintype "passive"))
      (node (ref "U5") (pin "5") (pinfunction "HVOUT20/45_5") (pintype "passive"))
    )
    (net (code "35") (name "/NX2-1") (class "Default")
      (node (ref "N2") (pin "3") (pinfunction "1_3") (pintype "passive"))
      (node (ref "U5") (pin "14") (pinfunction "HVOUT11/54_14") (pintype "passive"))
    )
    (net (code "36") (name "/NX2-2") (class "Default")
      (node (ref "N2") (pin "4") (pinfunction "2_4") (pintype "passive"))
      (node (ref "U5") (pin "13") (pinfunction "HVOUT12/53_13") (pintype "passive"))
    )
    (net (code "37") (name "/NX2-3") (class "Default")
      (node (ref "N2") (pin "5") (pinfunction "3_5") (pintype "passive"))
      (node (ref "U5") (pin "12") (pinfunction "HVOUT13/52_12") (pintype "passive"))
    )
    (net (code "38") (name "/NX2-4") (class "Default")
      (node (ref "N2") (pin "6") (pinfunction "4_6") (pintype "passive"))
      (node (ref "U5") (pin "11") (pinfunction "HVOUT14/51_11") (pintype "passive"))
    )
    (net (code "39") (name "/NX2-5") (class "Default")
      (node (ref "N2") (pin "7") (pinfunction "5_7") (pintype "passive"))
      (node (ref "U5") (pin "10") (pinfunction "HVOUT15/50_10") (pintype "passive"))
    )
    (net (code "40") (name "/NX2-6") (class "Default")
      (node (ref "N2") (pin "8") (pinfunction "6_8") (pintype "passive"))
      (node (ref "U5") (pin "9") (pinfunction "HVOUT16/49_9") (pintype "passive"))
    )
    (net (code "41") (name "/NX2-7") (class "Default")
      (node (ref "N2") (pin "9") (pinfunction "7_9") (pintype "passive"))
      (node (ref "U5") (pin "8") (pinfunction "HVOUT17/48_8") (pintype "passive"))
    )
    (net (code "42") (name "/NX2-8") (class "Default")
      (node (ref "N2") (pin "10") (pinfunction "8_10") (pintype "passive"))
      (node (ref "U5") (pin "7") (pinfunction "HVOUT18/47_7") (pintype "passive"))
    )
    (net (code "43") (name "/NX2-9") (class "Default")
      (node (ref "N2") (pin "11") (pinfunction "9_11") (pintype "passive"))
      (node (ref "U5") (pin "6") (pinfunction "HVOUT19/46_6") (pintype "passive"))
    )
    (net (code "44") (name "/NX3-0") (class "Default")
      (node (ref "N3") (pin "12") (pinfunction "0_12") (pintype "passive"))
      (node (ref "U5") (pin "75") (pinfunction "HVOUT30/35_75") (pintype "passive"))
    )
    (net (code "45") (name "/NX3-1") (class "Default")
      (node (ref "N3") (pin "3") (pinfunction "1_3") (pintype "passive"))
      (node (ref "U5") (pin "4") (pinfunction "HVOUT21/44_4") (pintype "passive"))
    )
    (net (code "46") (name "/NX3-2") (class "Default")
      (node (ref "N3") (pin "4") (pinfunction "2_4") (pintype "passive"))
      (node (ref "U5") (pin "3") (pinfunction "HVOUT22/43_3") (pintype "passive"))
    )
    (net (code "47") (name "/NX3-3") (class "Default")
      (node (ref "N3") (pin "5") (pinfunction "3_5") (pintype "passive"))
      (node (ref "U5") (pin "2") (pinfunction "HVOUT23/42_2") (pintype "passive"))
    )
    (net (code "48") (name "/NX3-4") (class "Default")
      (node (ref "N3") (pin "6") (pinfunction "4_6") (pintype "passive"))
      (node (ref "U5") (pin "1") (pinfunction "HVOUT24/41_1") (pintype "passive"))
    )
    (net (code "49") (name "/NX3-5") (class "Default")
      (node (ref "N3") (pin "7") (pinfunction "5_7") (pintype "passive"))
      (node (ref "U5") (pin "80") (pinfunction "HVOUT25/40_80") (pintype "passive"))
    )
    (net (code "50") (name "/NX3-6") (class "Default")
      (node (ref "N3") (pin "8") (pinfunction "6_8") (pintype "passive"))
      (node (ref "U5") (pin "79") (pinfunction "HVOUT26/39_79") (pintype "passive"))
    )
    (net (code "51") (name "/NX3-7") (class "Default")
      (node (ref "N3") (pin "9") (pinfunction "7_9") (pintype "passive"))
      (node (ref "U5") (pin "78") (pinfunction "HVOUT27/38_78") (pintype "passive"))
    )
    (net (code "52") (name "/NX3-8") (class "Default")
      (node (ref "N3") (pin "10") (pinfunction "8_10") (pintype "passive"))
      (node (ref "U5") (pin "77") (pinfunction "HVOUT28/37_77") (pintype "passive"))
    )
    (net (code "53") (name "/NX3-9") (class "Default")
      (node (ref "N3") (pin "11") (pinfunction "9_11") (pintype "passive"))
      (node (ref "U5") (pin "76") (pinfunction "HVOUT29/36_76") (pintype "passive"))
    )
    (net (code "54") (name "/NX4-0") (class "Default")
      (node (ref "N4") (pin "12") (pinfunction "0_12") (pintype "passive"))
      (node (ref "U5") (pin "65") (pinfunction "HVOUT40/25_65") (pintype "passive"))
    )
    (net (code "55") (name "/NX4-1") (class "Default")
      (node (ref "N4") (pin "3") (pinfunction "1_3") (pintype "passive"))
      (node (ref "U5") (pin "74") (pinfunction "HVOUT31/34_74") (pintype "passive"))
    )
    (net (code "56") (name "/NX4-2") (class "Default")
      (node (ref "N4") (pin "4") (pinfunction "2_4") (pintype "passive"))
      (node (ref "U5") (pin "73") (pinfunction "HVOUT32/33_73") (pintype "passive"))
    )
    (net (code "57") (name "/NX4-3") (class "Default")
      (node (ref "N4") (pin "5") (pinfunction "3_5") (pintype "passive"))
      (node (ref "U5") (pin "72") (pinfunction "HVOUT33/32_72") (pintype "passive"))
    )
    (net (code "58") (name "/NX4-4") (class "Default")
      (node (ref "N4") (pin "6") (pinfunction "4_6") (pintype "passive"))
      (node (ref "U5") (pin "71") (pinfunction "HVOUT34/31_71") (pintype "passive"))
    )
    (net (code "59") (name "/NX4-5") (class "Default")
      (node (ref "N4") (pin "7") (pinfunction "5_7") (pintype "passive"))
      (node (ref "U5") (pin "70") (pinfunction "HVOUT35/30_70") (pintype "passive"))
    )
    (net (code "60") (name "/NX4-6") (class "Default")
      (node (ref "N4") (pin "8") (pinfunction "6_8") (pintype "passive"))
      (node (ref "U5") (pin "69") (pinfunction "HVOUT36/29_69") (pintype "passive"))
    )
    (net (code "61") (name "/NX4-7") (class "Default")
      (node (ref "N4") (pin "9") (pinfunction "7_9") (pintype "passive"))
      (node (ref "U5") (pin "68") (pinfunction "HVOUT37/28_68") (pintype "passive"))
    )
    (net (code "62") (name "/NX4-8") (class "Default")
      (node (ref "N4") (pin "10") (pinfunction "8_10") (pintype "passive"))
      (node (ref "U5") (pin "67") (pinfunction "HVOUT38/27_67") (pintype "passive"))
    )
    (net (code "63") (name "/NX4-9") (class "Default")
      (node (ref "N4") (pin "11") (pinfunction "9_11") (pintype "passive"))
      (node (ref "U5") (pin "66") (pinfunction "HVOUT39/26_66") (pintype "passive"))
    )
    (net (code "64") (name "/NX5-0") (class "Default")
      (node (ref "N5") (pin "12") (pinfunction "0_12") (pintype "passive"))
      (node (ref "U5") (pin "55") (pinfunction "HVOUT50/15_55") (pintype "passive"))
    )
    (net (code "65") (name "/NX5-1") (class "Default")
      (node (ref "N5") (pin "3") (pinfunction "1_3") (pintype "passive"))
      (node (ref "U5") (pin "64") (pinfunction "HVOUT41/24_64") (pintype "passive"))
    )
    (net (code "66") (name "/NX5-2") (class "Default")
      (node (ref "N5") (pin "4") (pinfunction "2_4") (pintype "passive"))
      (node (ref "U5") (pin "63") (pinfunction "HVOUT42/23_63") (pintype "passive"))
    )
    (net (code "67") (name "/NX5-3") (class "Default")
      (node (ref "N5") (pin "5") (pinfunction "3_5") (pintype "passive"))
      (node (ref "U5") (pin "62") (pinfunction "HVOUT43/22_62") (pintype "passive"))
    )
    (net (code "68") (name "/NX5-4") (class "Default")
      (node (ref "N5") (pin "6") (pinfunction "4_6") (pintype "passive"))
      (node (ref "U5") (pin "61") (pinfunction "HVOUT44/21_61") (pintype "passive"))
    )
    (net (code "69") (name "/NX5-5") (class "Default")
      (node (ref "N5") (pin "7") (pinfunction "5_7") (pintype "passive"))
      (node (ref "U5") (pin "60") (pinfunction "HVOUT45/20_60") (pintype "passive"))
    )
    (net (code "70") (name "/NX5-6") (class "Default")
      (node (ref "N5") (pin "8") (pinfunction "6_8") (pintype "passive"))
      (node (ref "U5") (pin "59") (pinfunction "HVOUT46/19_59") (pintype "passive"))
    )
    (net (code "71") (name "/NX5-7") (class "Default")
      (node (ref "N5") (pin "9") (pinfunction "7_9") (pintype "passive"))
      (node (ref "U5") (pin "58") (pinfunction "HVOUT47/18_58") (pintype "passive"))
    )
    (net (code "72") (name "/NX5-8") (class "Default")
      (node (ref "N5") (pin "10") (pinfunction "8_10") (pintype "passive"))
      (node (ref "U5") (pin "57") (pinfunction "HVOUT48/17_57") (pintype "passive"))
    )
    (net (code "73") (name "/NX5-9") (class "Default")
      (node (ref "N5") (pin "11") (pinfunction "9_11") (pintype "passive"))
      (node (ref "U5") (pin "56") (pinfunction "HVOUT49/16_56") (pintype "passive"))
    )
    (net (code "74") (name "/NX6-0") (class "Default")
      (node (ref "N6") (pin "12") (pinfunction "0_12") (pintype "passive"))
      (node (ref "U5") (pin "45") (pinfunction "HVOUT60/5_45") (pintype "passive"))
    )
    (net (code "75") (name "/NX6-1") (class "Default")
      (node (ref "N6") (pin "3") (pinfunction "1_3") (pintype "passive"))
      (node (ref "U5") (pin "54") (pinfunction "HVOUT51/14_54") (pintype "passive"))
    )
    (net (code "76") (name "/NX6-2") (class "Default")
      (node (ref "N6") (pin "4") (pinfunction "2_4") (pintype "passive"))
      (node (ref "U5") (pin "53") (pinfunction "HVOUT52/13_53") (pintype "passive"))
    )
    (net (code "77") (name "/NX6-3") (class "Default")
      (node (ref "N6") (pin "5") (pinfunction "3_5") (pintype "passive"))
      (node (ref "U5") (pin "52") (pinfunction "HVOUT53/12_52") (pintype "passive"))
    )
    (net (code "78") (name "/NX6-4") (class "Default")
      (node (ref "N6") (pin "6") (pinfunction "4_6") (pintype "passive"))
      (node (ref "U5") (pin "51") (pinfunction "HVOUT54/11_51") (pintype "passive"))
    )
    (net (code "79") (name "/NX6-5") (class "Default")
      (node (ref "N6") (pin "7") (pinfunction "5_7") (pintype "passive"))
      (node (ref "U5") (pin "50") (pinfunction "HVOUT55/10_50") (pintype "passive"))
    )
    (net (code "80") (name "/NX6-6") (class "Default")
      (node (ref "N6") (pin "8") (pinfunction "6_8") (pintype "passive"))
      (node (ref "U5") (pin "49") (pinfunction "HVOUT56/9_49") (pintype "passive"))
    )
    (net (code "81") (name "/NX6-7") (class "Default")
      (node (ref "N6") (pin "9") (pinfunction "7_9") (pintype "passive"))
      (node (ref "U5") (pin "48") (pinfunction "HVOUT57/8_48") (pintype "passive"))
    )
    (net (code "82") (name "/NX6-8") (class "Default")
      (node (ref "N6") (pin "10") (pinfunction "8_10") (pintype "passive"))
      (node (ref "U5") (pin "47") (pinfunction "HVOUT58/7_47") (pintype "passive"))
    )
    (net (code "83") (name "/NX6-9") (class "Default")
      (node (ref "N6") (pin "11") (pinfunction "9_11") (pintype "passive"))
      (node (ref "U5") (pin "46") (pinfunction "HVOUT59/6_46") (pintype "passive"))
    )
    (net (code "84") (name "/ON{slash}OFF") (class "Default")
      (node (ref "R2") (pin "2") (pinfunction "2_2") (pintype "passive"))
      (node (ref "U1") (pin "55") (pinfunction "PB3/JTDO_55") (pintype "bidirectional"))
    )
    (net (code "85") (name "/OSC_IN") (class "Default")
      (node (ref "C19") (pin "2") (pinfunction "2_2") (pintype "passive"))
      (node (ref "R25") (pin "2") (pinfunction "2_2") (pintype "passive"))
      (node (ref "U1") (pin "5") (pinfunction "OSC_IN/PD0_5") (pintype "input"))
      (node (ref "Y1") (pin "2") (pinfunction "OSC2_2") (pintype "passive"))
    )
    (net (code "86") (name "/OSC_OUT") (class "Default")
      (node (ref "C20") (pin "2") (pinfunction "2_2") (pintype "passive"))
      (node (ref "R25") (pin "1") (pinfunction "1_1") (pintype "passive"))
      (node (ref "U1") (pin "6") (pinfunction "OSC_OUT/PD1_6") (pintype "output"))
      (node (ref "Y1") (pin "1") (pinfunction "OSC1_1") (pintype "passive"))
    )
    (net (code "87") (name "/RESET") (class "Default")
      (node (ref "C18") (pin "1") (pinfunction "1_1") (pintype "passive"))
      (node (ref "R20") (pin "1") (pinfunction "1_1") (pintype "passive"))
      (node (ref "RST") (pin "1") (pinfunction "1_1") (pintype "passive"))
      (node (ref "U1") (pin "7") (pinfunction "NRST_7") (pintype "bidirectional"))
    )
    (net (code "88") (name "/SCL") (class "Default")
      (node (ref "R30") (pin "1") (pinfunction "1_1") (pintype "passive"))
      (node (ref "U1") (pin "37") (pinfunction "PC6_37") (pintype "bidirectional"))
      (node (ref "U6") (pin "16") (pinfunction "SCL_16") (pintype "passive"))
      (node (ref "U7") (pin "4") (pinfunction "SCL_4") (pintype "passive"))
    )
    (net (code "89") (name "/SDA") (class "Default")
      (node (ref "R29") (pin "1") (pinfunction "1_1") (pintype "passive"))
      (node (ref "U1") (pin "38") (pinfunction "PC7_38") (pintype "bidirectional"))
      (node (ref "U6") (pin "15") (pinfunction "SDA_15") (pintype "passive"))
      (node (ref "U7") (pin "1") (pinfunction "SDA_1") (pintype "passive"))
    )
    (net (code "90") (name "/SWCLK") (class "Default")
      (node (ref "P1") (pin "4") (pinfunction "4_4") (pintype "passive"))
      (node (ref "U1") (pin "49") (pinfunction "PA14/JTCK/SWCLK_49") (pintype "bidirectional"))
    )
    (net (code "91") (name "/SWDIO") (class "Default")
      (node (ref "P1") (pin "3") (pinfunction "3_3") (pintype "passive"))
      (node (ref "U1") (pin "46") (pinfunction "PA13/JTMS/SWDIO_46") (pintype "bidirectional"))
    )
    (net (code "92") (name "/USB_D+") (class "Default")
      (node (ref "J1") (pin "3") (pinfunction "D+_3") (pintype "passive"))
      (node (ref "R22") (pin "1") (pinfunction "1_1") (pintype "passive"))
      (node (ref "R24") (pin "1") (pinfunction "1_1") (pintype "passive"))
    )
    (net (code "93") (name "/USB_D-") (class "Default")
      (node (ref "J1") (pin "2") (pinfunction "D-_2") (pintype "passive"))
      (node (ref "R21") (pin "1") (pinfunction "1_1") (pintype "passive"))
    )
    (net (code "94") (name "GND") (class "Default")
      (node (ref "BT") (pin "2") (pintype "passive"))
      (node (ref "C1") (pin "2") (pinfunction "2_2") (pintype "passive"))
      (node (ref "C10") (pin "2") (pinfunction "2_2") (pintype "passive"))
      (node (ref "C11") (pin "2") (pinfunction "2_2") (pintype "passive"))
      (node (ref "C12") (pin "1") (pinfunction "1_1") (pintype "passive"))
      (node (ref "C13") (pin "1") (pinfunction "1_1") (pintype "passive"))
      (node (ref "C14") (pin "1") (pinfunction "1_1") (pintype "passive"))
      (node (ref "C15") (pin "1") (pinfunction "1_1") (pintype "passive"))
      (node (ref "C16") (pin "1") (pinfunction "1_1") (pintype "passive"))
      (node (ref "C17") (pin "2") (pinfunction "2_2") (pintype "passive"))
      (node (ref "C18") (pin "2") (pinfunction "2_2") (pintype "passive"))
      (node (ref "C19") (pin "1") (pinfunction "1_1") (pintype "passive"))
      (node (ref "C2") (pin "2") (pinfunction "2_2") (pintype "passive"))
      (node (ref "C20") (pin "1") (pinfunction "1_1") (pintype "passive"))
      (node (ref "C21") (pin "1") (pinfunction "1_1") (pintype "passive"))
      (node (ref "C22") (pin "1") (pinfunction "1_1") (pintype "passive"))
      (node (ref "C23") (pin "2") (pinfunction "2_2") (pintype "passive"))
      (node (ref "C24") (pin "2") (pinfunction "2_2") (pintype "passive"))
      (node (ref "C25") (pin "2") (pinfunction "2_2") (pintype "passive"))
      (node (ref "C26") (pin "2") (pinfunction "2_2") (pintype "passive"))
      (node (ref "C27") (pin "2") (pinfunction "2_2") (pintype "passive"))
      (node (ref "C28") (pin "2") (pinfunction "2_2") (pintype "passive"))
      (node (ref "C29") (pin "2") (pinfunction "2_2") (pintype "passive"))
      (node (ref "C3") (pin "2") (pinfunction "2_2") (pintype "passive"))
      (node (ref "C4") (pin "2") (pinfunction "2_2") (pintype "passive"))
      (node (ref "C7") (pin "2") (pinfunction "2_2") (pintype "passive"))
      (node (ref "C8") (pin "2") (pinfunction "2_2") (pintype "passive"))
      (node (ref "C9") (pin "2") (pinfunction "2_2") (pintype "passive"))
      (node (ref "J1") (pin "5") (pinfunction "VSS_5") (pintype "passive"))
      (node (ref "KEY0") (pin "2") (pinfunction "2_2") (pintype "passive"))
      (node (ref "KEY1") (pin "2") (pinfunction "2_2") (pintype "passive"))
      (node (ref "KEY2") (pin "2") (pinfunction "2_2") (pintype "passive"))
      (node (ref "P1") (pin "2") (pinfunction "2_2") (pintype "passive"))
      (node (ref "Q5") (pin "2") (pinfunction "E_2") (pintype "passive"))
      (node (ref "Q6") (pin "2") (pinfunction "E_2") (pintype "passive"))
      (node (ref "R23") (pin "1") (pinfunction "1_1") (pintype "passive"))
      (node (ref "R26") (pin "2") (pinfunction "2_2") (pintype "passive"))
      (node (ref "RGB1") (pin "3") (pinfunction "VSS_3") (pintype "passive"))
      (node (ref "RGB2") (pin "3") (pinfunction "VSS_3") (pintype "passive"))
      (node (ref "RGB3") (pin "3") (pinfunction "VSS_3") (pintype "passive"))
      (node (ref "RGB4") (pin "3") (pinfunction "VSS_3") (pintype "passive"))
      (node (ref "RGB5") (pin "3") (pinfunction "VSS_3") (pintype "passive"))
      (node (ref "RGB6") (pin "3") (pinfunction "VSS_3") (pintype "passive"))
      (node (ref "RST") (pin "2") (pinfunction "2_2") (pintype "passive"))
      (node (ref "U1") (pin "12") (pinfunction "VSSA_12") (pintype "power_in"))
      (node (ref "U1") (pin "18") (pinfunction "VSS_4_18") (pintype "power_in"))
      (node (ref "U1") (pin "31") (pinfunction "VSS_1_31") (pintype "power_in"))
      (node (ref "U1") (pin "47") (pinfunction "VSS_2_47") (pintype "power_in"))
      (node (ref "U1") (pin "63") (pinfunction "VSS_3_63") (pintype "power_in"))
      (node (ref "U2") (pin "1") (pinfunction "GND_1") (pintype "passive"))
      (node (ref "U3") (pin "1") (pinfunction "GND_1") (pintype "passive"))
      (node (ref "U4") (pin "2") (pinfunction "GND_2") (pintype "passive"))
      (node (ref "U5") (pin "34") (pinfunction "GND_34") (pintype "passive"))
      (node (ref "U6") (pin "10") (pinfunction "N.C._10") (pintype "passive"))
      (node (ref "U6") (pin "11") (pinfunction "N.C._11") (pintype "passive"))
      (node (ref "U6") (pin "12") (pinfunction "N.C._12") (pintype "passive"))
      (node (ref "U6") (pin "13") (pinfunction "GND_13") (pintype "passive"))
      (node (ref "U6") (pin "5") (pinfunction "N.C._5") (pintype "passive"))
      (node (ref "U6") (pin "6") (pinfunction "N.C._6") (pintype "passive"))
      (node (ref "U6") (pin "7") (pinfunction "N.C._7") (pintype "passive"))
      (node (ref "U6") (pin "8") (pinfunction "N.C._8") (pintype "passive"))
      (node (ref "U6") (pin "9") (pinfunction "N.C._9") (pintype "passive"))
      (node (ref "U7") (pin "2") (pinfunction "ADDR_2") (pintype "passive"))
      (node (ref "U7") (pin "7") (pinfunction "R_7") (pintype "passive"))
      (node (ref "U7") (pin "8") (pinfunction "VSS_8") (pintype "passive"))
      (node (ref "U7") (pin "9") (pinfunction "PAD_9") (pintype "passive"))
      (node (ref "U8") (pin "13") (pinfunction "GND_13") (pintype "passive"))
    )
    (net (code "95") (name "GNDH") (class "Default")
      (node (ref "D2") (pin "1") (pinfunction "A_1") (pintype "passive"))
      (node (ref "Q1") (pin "2") (pinfunction "E_2") (pintype "passive"))
      (node (ref "Q2") (pin "2") (pinfunction "E_2") (pintype "passive"))
      (node (ref "Q3") (pin "2") (pinfunction "E_2") (pintype "passive"))
      (node (ref "Q4") (pin "2") (pinfunction "E_2") (pintype "passive"))
      (node (ref "U4") (pin "3") (pinfunction "GNDH_3") (pintype "passive"))
    )
    (net (code "96") (name "Net-(B-1)") (class "Default")
      (node (ref "B") (pin "2") (pinfunction "1_2") (pintype "passive"))
      (node (ref "Q6") (pin "3") (pinfunction "C_3") (pintype "passive"))
    )
    (net (code "97") (name "Net-(D2-K)") (class "Default")
      (node (ref "D2") (pin "2") (pinfunction "K_2") (pintype "passive"))
      (node (ref "R31") (pin "2") (pinfunction "2_2") (pintype "passive"))
      (node (ref "U5") (pin "40") (pinfunction "VPP_40") (pintype "passive"))
    )
    (net (code "98") (name "Net-(D3-K)") (class "Default")
      (node (ref "D3") (pin "2") (pinfunction "K_2") (pintype "passive"))
      (node (ref "R32") (pin "2") (pinfunction "2_2") (pintype "passive"))
    )
    (net (code "99") (name "Net-(DS1-Pad2)") (class "Default")
      (node (ref "DS1") (pin "2") (pintype "passive"))
      (node (ref "R12") (pin "2") (pinfunction "2_2") (pintype "passive"))
    )
    (net (code "100") (name "Net-(DS2-Pad2)") (class "Default")
      (node (ref "DS2") (pin "2") (pintype "passive"))
      (node (ref "R13") (pin "2") (pinfunction "2_2") (pintype "passive"))
    )
    (net (code "101") (name "Net-(DS3-Pad2)") (class "Default")
      (node (ref "DS3") (pin "2") (pintype "passive"))
      (node (ref "R14") (pin "1") (pinfunction "1_1") (pintype "passive"))
    )
    (net (code "102") (name "Net-(DS4-Pad2)") (class "Default")
      (node (ref "DS4") (pin "2") (pintype "passive"))
      (node (ref "R15") (pin "2") (pinfunction "2_2") (pintype "passive"))
    )
    (net (code "103") (name "Net-(J1-VCC)") (class "Default")
      (node (ref "F1") (pin "1") (pinfunction "1_1") (pintype "passive"))
      (node (ref "J1") (pin "1") (pinfunction "VCC_1") (pintype "passive"))
    )
    (net (code "104") (name "Net-(N1-VCC)") (class "Default")
      (node (ref "N1") (pin "1") (pinfunction "VCC_1") (pintype "passive"))
      (node (ref "R6") (pin "1") (pinfunction "1_1") (pintype "passive"))
    )
    (net (code "105") (name "Net-(N2-VCC)") (class "Default")
      (node (ref "N2") (pin "1") (pinfunction "VCC_1") (pintype "passive"))
      (node (ref "R7") (pin "1") (pinfunction "1_1") (pintype "passive"))
    )
    (net (code "106") (name "Net-(N3-VCC)") (class "Default")
      (node (ref "N3") (pin "1") (pinfunction "VCC_1") (pintype "passive"))
      (node (ref "R8") (pin "1") (pinfunction "1_1") (pintype "passive"))
    )
    (net (code "107") (name "Net-(N4-VCC)") (class "Default")
      (node (ref "N4") (pin "1") (pinfunction "VCC_1") (pintype "passive"))
      (node (ref "R9") (pin "1") (pinfunction "1_1") (pintype "passive"))
    )
    (net (code "108") (name "Net-(N5-VCC)") (class "Default")
      (node (ref "N5") (pin "1") (pinfunction "VCC_1") (pintype "passive"))
      (node (ref "R10") (pin "1") (pinfunction "1_1") (pintype "passive"))
    )
    (net (code "109") (name "Net-(N6-VCC)") (class "Default")
      (node (ref "N6") (pin "1") (pinfunction "VCC_1") (pintype "passive"))
      (node (ref "R11") (pin "1") (pinfunction "1_1") (pintype "passive"))
    )
    (net (code "110") (name "Net-(Q1-B)") (class "Default")
      (node (ref "Q1") (pin "1") (pinfunction "B_1") (pintype "passive"))
      (node (ref "R16") (pin "2") (pinfunction "2_2") (pintype "passive"))
    )
    (net (code "111") (name "Net-(Q1-C)") (class "Default")
      (node (ref "DS1") (pin "1") (pintype "passive"))
      (node (ref "Q1") (pin "3") (pinfunction "C_3") (pintype "passive"))
    )
    (net (code "112") (name "Net-(Q2-B)") (class "Default")
      (node (ref "Q2") (pin "1") (pinfunction "B_1") (pintype "passive"))
      (node (ref "R17") (pin "2") (pinfunction "2_2") (pintype "passive"))
    )
    (net (code "113") (name "Net-(Q2-C)") (class "Default")
      (node (ref "DS2") (pin "1") (pintype "passive"))
      (node (ref "Q2") (pin "3") (pinfunction "C_3") (pintype "passive"))
    )
    (net (code "114") (name "Net-(Q3-B)") (class "Default")
      (node (ref "Q3") (pin "1") (pinfunction "B_1") (pintype "passive"))
      (node (ref "R18") (pin "2") (pinfunction "2_2") (pintype "passive"))
    )
    (net (code "115") (name "Net-(Q3-C)") (class "Default")
      (node (ref "DS3") (pin "1") (pintype "passive"))
      (node (ref "Q3") (pin "3") (pinfunction "C_3") (pintype "passive"))
    )
    (net (code "116") (name "Net-(Q4-B)") (class "Default")
      (node (ref "Q4") (pin "1") (pinfunction "B_1") (pintype "passive"))
      (node (ref "R19") (pin "2") (pinfunction "2_2") (pintype "passive"))
    )
    (net (code "117") (name "Net-(Q4-C)") (class "Default")
      (node (ref "DS4") (pin "1") (pintype "passive"))
      (node (ref "Q4") (pin "3") (pinfunction "C_3") (pintype "passive"))
    )
    (net (code "118") (name "Net-(Q5-B)") (class "Default")
      (node (ref "Q5") (pin "1") (pinfunction "B_1") (pintype "passive"))
      (node (ref "R2") (pin "1") (pinfunction "1_1") (pintype "passive"))
    )
    (net (code "119") (name "Net-(Q5-C)") (class "Default")
      (node (ref "Q5") (pin "3") (pinfunction "C_3") (pintype "passive"))
      (node (ref "U9") (pin "2") (pinfunction "2_2") (pintype "passive"))
    )
    (net (code "120") (name "Net-(Q6-B)") (class "Default")
      (node (ref "Q6") (pin "1") (pinfunction "B_1") (pintype "passive"))
      (node (ref "R27") (pin "2") (pinfunction "2_2") (pintype "passive"))
    )
    (net (code "121") (name "Net-(R1-Pad2)") (class "Default")
      (node (ref "R1") (pin "2") (pinfunction "2_2") (pintype "passive"))
      (node (ref "U9") (pin "1") (pinfunction "1_1") (pintype "passive"))
    )
    (net (code "122") (name "Net-(RGB1-DO)") (class "Default")
      (node (ref "RGB1") (pin "2") (pinfunction "DO_2") (pintype "passive"))
      (node (ref "RGB2") (pin "4") (pinfunction "DI_4") (pintype "passive"))
    )
    (net (code "123") (name "Net-(RGB2-DO)") (class "Default")
      (node (ref "RGB2") (pin "2") (pinfunction "DO_2") (pintype "passive"))
      (node (ref "RGB3") (pin "4") (pinfunction "DI_4") (pintype "passive"))
    )
    (net (code "124") (name "Net-(RGB3-DO)") (class "Default")
      (node (ref "RGB3") (pin "2") (pinfunction "DO_2") (pintype "passive"))
      (node (ref "RGB4") (pin "4") (pinfunction "DI_4") (pintype "passive"))
    )
    (net (code "125") (name "Net-(RGB4-DO)") (class "Default")
      (node (ref "RGB4") (pin "2") (pinfunction "DO_2") (pintype "passive"))
      (node (ref "RGB5") (pin "4") (pinfunction "DI_4") (pintype "passive"))
    )
    (net (code "126") (name "Net-(RGB5-DO)") (class "Default")
      (node (ref "RGB5") (pin "2") (pinfunction "DO_2") (pintype "passive"))
      (node (ref "RGB6") (pin "4") (pinfunction "DI_4") (pintype "passive"))
    )
    (net (code "127") (name "Net-(U1-BOOT0)") (class "Default")
      (node (ref "R23") (pin "2") (pinfunction "2_2") (pintype "passive"))
      (node (ref "U1") (pin "60") (pinfunction "BOOT0_60") (pintype "input"))
    )
    (net (code "128") (name "Net-(U1-PA11)") (class "Default")
      (node (ref "R21") (pin "2") (pinfunction "2_2") (pintype "passive"))
      (node (ref "U1") (pin "44") (pinfunction "PA11_44") (pintype "bidirectional"))
    )
    (net (code "129") (name "Net-(U1-PA12)") (class "Default")
      (node (ref "R22") (pin "2") (pinfunction "2_2") (pintype "passive"))
      (node (ref "U1") (pin "45") (pinfunction "PA12_45") (pintype "bidirectional"))
    )
    (net (code "130") (name "Net-(U1-PB2{slash}BOOT1)") (class "Default")
      (node (ref "R26") (pin "1") (pinfunction "1_1") (pintype "passive"))
      (node (ref "U1") (pin "28") (pinfunction "PB2/BOOT1_28") (pintype "bidirectional"))
    )
    (net (code "131") (name "Net-(U2-IN)") (class "Default")
      (node (ref "C1") (pin "1") (pinfunction "1_1") (pintype "passive"))
      (node (ref "C2") (pin "1") (pinfunction "1_1") (pintype "passive"))
      (node (ref "FB1") (pin "2") (pinfunction "2_2") (pintype "passive"))
      (node (ref "U2") (pin "3") (pinfunction "IN_3") (pintype "passive"))
    )
    (net (code "132") (name "Net-(U4-+5V)") (class "Default")
      (node (ref "U4") (pin "1") (pinfunction "+5V_1") (pintype "passive"))
      (node (ref "U9") (pin "3") (pinfunction "3_3") (pintype "passive"))
    )
    (net (code "133") (name "Net-(U6-VBAT)") (class "Default")
      (node (ref "BT") (pin "1") (pintype "passive"))
      (node (ref "U6") (pin "14") (pinfunction "VBAT_14") (pintype "passive"))
    )
    (net (code "134") (name "VCC3.3") (class "Default")
      (node (ref "B") (pin "1") (pinfunction "0_1") (pintype "passive"))
      (node (ref "C10") (pin "1") (pinfunction "1_1") (pintype "passive"))
      (node (ref "C12") (pin "2") (pinfunction "2_2") (pintype "passive"))
      (node (ref "C13") (pin "2") (pinfunction "2_2") (pintype "passive"))
      (node (ref "C14") (pin "2") (pinfunction "2_2") (pintype "passive"))
      (node (ref "C15") (pin "2") (pinfunction "2_2") (pintype "passive"))
      (node (ref "C16") (pin "2") (pinfunction "2_2") (pintype "passive"))
      (node (ref "C17") (pin "1") (pinfunction "1_1") (pintype "passive"))
      (node (ref "C21") (pin "2") (pinfunction "2_2") (pintype "passive"))
      (node (ref "C22") (pin "2") (pinfunction "2_2") (pintype "passive"))
      (node (ref "C23") (pin "1") (pinfunction "1_1") (pintype "passive"))
      (node (ref "C9") (pin "1") (pinfunction "1_1") (pintype "passive"))
      (node (ref "D3") (pin "1") (pinfunction "A_1") (pintype "passive"))
      (node (ref "P1") (pin "1") (pinfunction "1_1") (pintype "passive"))
      (node (ref "R20") (pin "2") (pinfunction "2_2") (pintype "passive"))
      (node (ref "R24") (pin "2") (pinfunction "2_2") (pintype "passive"))
      (node (ref "R28") (pin "2") (pinfunction "2_2") (pintype "passive"))
      (node (ref "R29") (pin "2") (pinfunction "2_2") (pintype "passive"))
      (node (ref "R30") (pin "2") (pinfunction "2_2") (pintype "passive"))
      (node (ref "U1") (pin "1") (pinfunction "VBAT_1") (pintype "power_in"))
      (node (ref "U1") (pin "13") (pinfunction "VDDA_13") (pintype "power_in"))
      (node (ref "U1") (pin "19") (pinfunction "VDD_4_19") (pintype "power_in"))
      (node (ref "U1") (pin "32") (pinfunction "VDD_1_32") (pintype "power_in"))
      (node (ref "U1") (pin "48") (pinfunction "VDD_2_48") (pintype "power_in"))
      (node (ref "U1") (pin "64") (pinfunction "VDD_3_64") (pintype "power_in"))
      (node (ref "U3") (pin "2") (pinfunction "OUT_2") (pintype "passive"))
      (node (ref "U6") (pin "2") (pinfunction "VCC_2") (pintype "passive"))
      (node (ref "U7") (pin "5") (pinfunction "VDD_5") (pintype "passive"))
      (node (ref "U7") (pin "6") (pinfunction "nRESET_6") (pintype "passive"))
      (node (ref "U8") (pin "12") (pinfunction "3.3V_12") (pintype "passive"))
    )
    (net (code "135") (name "VCC5") (class "Default")
      (node (ref "C11") (pin "1") (pinfunction "1_1") (pintype "passive"))
      (node (ref "C24") (pin "1") (pinfunction "1_1") (pintype "passive"))
      (node (ref "C25") (pin "1") (pinfunction "1_1") (pintype "passive"))
      (node (ref "C26") (pin "1") (pinfunction "1_1") (pintype "passive"))
      (node (ref "C27") (pin "1") (pinfunction "1_1") (pintype "passive"))
      (node (ref "C28") (pin "1") (pinfunction "1_1") (pintype "passive"))
      (node (ref "C29") (pin "1") (pinfunction "1_1") (pintype "passive"))
      (node (ref "C3") (pin "1") (pinfunction "1_1") (pintype "passive"))
      (node (ref "C4") (pin "1") (pinfunction "1_1") (pintype "passive"))
      (node (ref "C7") (pin "1") (pinfunction "1_1") (pintype "passive"))
      (node (ref "C8") (pin "1") (pinfunction "1_1") (pintype "passive"))
      (node (ref "R1") (pin "1") (pinfunction "1_1") (pintype "passive"))
      (node (ref "R33") (pin "2") (pinfunction "2_2") (pintype "passive"))
      (node (ref "R34") (pin "2") (pinfunction "2_2") (pintype "passive"))
      (node (ref "R35") (pin "2") (pinfunction "2_2") (pintype "passive"))
      (node (ref "R36") (pin "2") (pinfunction "2_2") (pintype "passive"))
      (node (ref "R37") (pin "2") (pinfunction "2_2") (pintype "passive"))
      (node (ref "R38") (pin "2") (pinfunction "2_2") (pintype "passive"))
      (node (ref "R39") (pin "2") (pinfunction "2_2") (pintype "passive"))
      (node (ref "RGB1") (pin "1") (pinfunction "VDD_1") (pintype "passive"))
      (node (ref "RGB2") (pin "1") (pinfunction "VDD_1") (pintype "passive"))
      (node (ref "RGB3") (pin "1") (pinfunction "VDD_1") (pintype "passive"))
      (node (ref "RGB4") (pin "1") (pinfunction "VDD_1") (pintype "passive"))
      (node (ref "RGB5") (pin "1") (pinfunction "VDD_1") (pintype "passive"))
      (node (ref "RGB6") (pin "1") (pinfunction "VDD_1") (pintype "passive"))
      (node (ref "U2") (pin "2") (pinfunction "OUT_2") (pintype "passive"))
      (node (ref "U3") (pin "3") (pinfunction "IN_3") (pintype "passive"))
      (node (ref "U5") (pin "31") (pinfunction "~{BL}_31") (pintype "passive"))
      (node (ref "U5") (pin "32") (pinfunction "VDD_32") (pintype "passive"))
      (node (ref "U5") (pin "33") (pinfunction "DIR_33") (pintype "passive"))
    )
    (net (code "136") (name "VCCH") (class "Default")
      (node (ref "R10") (pin "2") (pinfunction "2_2") (pintype "passive"))
      (node (ref "R11") (pin "2") (pinfunction "2_2") (pintype "passive"))
      (node (ref "R12") (pin "1") (pinfunction "1_1") (pintype "passive"))
      (node (ref "R13") (pin "1") (pinfunction "1_1") (pintype "passive"))
      (node (ref "R14") (pin "2") (pinfunction "2_2") (pintype "passive"))
      (node (ref "R15") (pin "1") (pinfunction "1_1") (pintype "passive"))
      (node (ref "R31") (pin "1") (pinfunction "1_1") (pintype "passive"))
      (node (ref "R6") (pin "2") (pinfunction "2_2") (pintype "passive"))
      (node (ref "R7") (pin "2") (pinfunction "2_2") (pintype "passive"))
      (node (ref "R8") (pin "2") (pinfunction "2_2") (pintype "passive"))
      (node (ref "R9") (pin "2") (pinfunction "2_2") (pintype "passive"))
      (node (ref "U4") (pin "4") (pinfunction "VCCH_4") (pintype "passive"))
    )
    (net (code "137") (name "unconnected-(J1-ID-Pad4)") (class "Default")
      (node (ref "J1") (pin "4") (pinfunction "ID_4") (pintype "passive+no_connect"))
    )
    (net (code "138") (name "unconnected-(N1-LP-Pad2)") (class "Default")
      (node (ref "N1") (pin "2") (pinfunction "LP_2") (pintype "passive"))
    )
    (net (code "139") (name "unconnected-(N1-RP-Pad13)") (class "Default")
      (node (ref "N1") (pin "13") (pinfunction "RP_13") (pintype "passive"))
    )
    (net (code "140") (name "unconnected-(N2-LP-Pad2)") (class "Default")
      (node (ref "N2") (pin "2") (pinfunction "LP_2") (pintype "passive"))
    )
    (net (code "141") (name "unconnected-(N2-RP-Pad13)") (class "Default")
      (node (ref "N2") (pin "13") (pinfunction "RP_13") (pintype "passive"))
    )
    (net (code "142") (name "unconnected-(N3-LP-Pad2)") (class "Default")
      (node (ref "N3") (pin "2") (pinfunction "LP_2") (pintype "passive"))
    )
    (net (code "143") (name "unconnected-(N3-RP-Pad13)") (class "Default")
      (node (ref "N3") (pin "13") (pinfunction "RP_13") (pintype "passive"))
    )
    (net (code "144") (name "unconnected-(N4-LP-Pad2)") (class "Default")
      (node (ref "N4") (pin "2") (pinfunction "LP_2") (pintype "passive"))
    )
    (net (code "145") (name "unconnected-(N4-RP-Pad13)") (class "Default")
      (node (ref "N4") (pin "13") (pinfunction "RP_13") (pintype "passive"))
    )
    (net (code "146") (name "unconnected-(N5-LP-Pad2)") (class "Default")
      (node (ref "N5") (pin "2") (pinfunction "LP_2") (pintype "passive"))
    )
    (net (code "147") (name "unconnected-(N5-RP-Pad13)") (class "Default")
      (node (ref "N5") (pin "13") (pinfunction "RP_13") (pintype "passive"))
    )
    (net (code "148") (name "unconnected-(N6-LP-Pad2)") (class "Default")
      (node (ref "N6") (pin "2") (pinfunction "LP_2") (pintype "passive"))
    )
    (net (code "149") (name "unconnected-(N6-RP-Pad13)") (class "Default")
      (node (ref "N6") (pin "13") (pinfunction "RP_13") (pintype "passive"))
    )
    (net (code "150") (name "unconnected-(RGB6-DO-Pad2)") (class "Default")
      (node (ref "RGB6") (pin "2") (pinfunction "DO_2") (pintype "passive"))
    )
    (net (code "151") (name "unconnected-(U1-PA2-Pad16)") (class "Default")
      (node (ref "U1") (pin "16") (pinfunction "PA2_16") (pintype "bidirectional"))
    )
    (net (code "152") (name "unconnected-(U1-PA3-Pad17)") (class "Default")
      (node (ref "U1") (pin "17") (pinfunction "PA3_17") (pintype "bidirectional"))
    )
    (net (code "153") (name "unconnected-(U1-PA7-Pad23)") (class "Default")
      (node (ref "U1") (pin "23") (pinfunction "PA7_23") (pintype "bidirectional"))
    )
    (net (code "154") (name "unconnected-(U1-PA8-Pad41)") (class "Default")
      (node (ref "U1") (pin "41") (pinfunction "PA8_41") (pintype "bidirectional"))
    )
    (net (code "155") (name "unconnected-(U1-PA15{slash}JTDI-Pad50)") (class "Default")
      (node (ref "U1") (pin "50") (pinfunction "PA15/JTDI_50") (pintype "bidirectional"))
    )
    (net (code "156") (name "unconnected-(U1-PB0-Pad26)") (class "Default")
      (node (ref "U1") (pin "26") (pinfunction "PB0_26") (pintype "bidirectional"))
    )
    (net (code "157") (name "unconnected-(U1-PB1-Pad27)") (class "Default")
      (node (ref "U1") (pin "27") (pinfunction "PB1_27") (pintype "bidirectional"))
    )
    (net (code "158") (name "unconnected-(U1-PB4{slash}JNTRST-Pad56)") (class "Default")
      (node (ref "U1") (pin "56") (pinfunction "PB4/JNTRST_56") (pintype "bidirectional"))
    )
    (net (code "159") (name "unconnected-(U1-PB6-Pad58)") (class "Default")
      (node (ref "U1") (pin "58") (pinfunction "PB6_58") (pintype "bidirectional"))
    )
    (net (code "160") (name "unconnected-(U1-PB7-Pad59)") (class "Default")
      (node (ref "U1") (pin "59") (pinfunction "PB7_59") (pintype "bidirectional"))
    )
    (net (code "161") (name "unconnected-(U1-PB8-Pad61)") (class "Default")
      (node (ref "U1") (pin "61") (pinfunction "PB8_61") (pintype "bidirectional"))
    )
    (net (code "162") (name "unconnected-(U1-PB9-Pad62)") (class "Default")
      (node (ref "U1") (pin "62") (pinfunction "PB9_62") (pintype "bidirectional"))
    )
    (net (code "163") (name "unconnected-(U1-PB10-Pad29)") (class "Default")
      (node (ref "U1") (pin "29") (pinfunction "PB10_29") (pintype "bidirectional"))
    )
    (net (code "164") (name "unconnected-(U1-PB11-Pad30)") (class "Default")
      (node (ref "U1") (pin "30") (pinfunction "PB11_30") (pintype "bidirectional"))
    )
    (net (code "165") (name "unconnected-(U1-PC4-Pad24)") (class "Default")
      (node (ref "U1") (pin "24") (pinfunction "PC4_24") (pintype "bidirectional"))
    )
    (net (code "166") (name "unconnected-(U1-PC5-Pad25)") (class "Default")
      (node (ref "U1") (pin "25") (pinfunction "PC5_25") (pintype "bidirectional"))
    )
    (net (code "167") (name "unconnected-(U1-PC14-OSC32_IN-Pad3)") (class "Default")
      (node (ref "U1") (pin "3") (pinfunction "PC14-OSC32_IN_3") (pintype "bidirectional"))
    )
    (net (code "168") (name "unconnected-(U1-PC15-OSC32_OUT-Pad4)") (class "Default")
      (node (ref "U1") (pin "4") (pinfunction "PC15-OSC32_OUT_4") (pintype "bidirectional"))
    )
    (net (code "169") (name "unconnected-(U1-PD2-Pad54)") (class "Default")
      (node (ref "U1") (pin "54") (pinfunction "PD2_54") (pintype "bidirectional"))
    )
    (net (code "170") (name "unconnected-(U5-DOUT1{slash}DIN4(B)-Pad39)") (class "Default")
      (node (ref "U5") (pin "39") (pinfunction "DOUT1/DIN4(B)_39") (pintype "passive"))
    )
    (net (code "171") (name "unconnected-(U5-DOUT2{slash}DIN3(B)-Pad38)") (class "Default")
      (node (ref "U5") (pin "38") (pinfunction "DOUT2/DIN3(B)_38") (pintype "passive"))
    )
    (net (code "172") (name "unconnected-(U5-DOUT3{slash}DIN2(B)-Pad37)") (class "Default")
      (node (ref "U5") (pin "37") (pinfunction "DOUT3/DIN2(B)_37") (pintype "passive"))
    )
    (net (code "173") (name "unconnected-(U5-DOUT4{slash}DIN1(B)-Pad36)") (class "Default")
      (node (ref "U5") (pin "36") (pinfunction "DOUT4/DIN1(B)_36") (pintype "passive"))
    )
    (net (code "174") (name "unconnected-(U5-HVOUT61{slash}4-Pad44)") (class "Default")
      (node (ref "U5") (pin "44") (pinfunction "HVOUT61/4_44") (pintype "passive"))
    )
    (net (code "175") (name "unconnected-(U5-HVOUT62{slash}3-Pad43)") (class "Default")
      (node (ref "U5") (pin "43") (pinfunction "HVOUT62/3_43") (pintype "passive"))
    )
    (net (code "176") (name "unconnected-(U5-HVOUT63{slash}2-Pad42)") (class "Default")
      (node (ref "U5") (pin "42") (pinfunction "HVOUT63/2_42") (pintype "passive"))
    )
    (net (code "177") (name "unconnected-(U5-HVOUT64{slash}1-Pad41)") (class "Default")
      (node (ref "U5") (pin "41") (pinfunction "HVOUT64/1_41") (pintype "passive"))
    )
    (net (code "178") (name "unconnected-(U6-32kHz-Pad1)") (class "Default")
      (node (ref "U6") (pin "1") (pinfunction "32kHz_1") (pintype "passive"))
    )
    (net (code "179") (name "unconnected-(U6-~{RST}-Pad4)") (class "Default")
      (node (ref "U6") (pin "4") (pinfunction "~{RST}_4") (pintype "passive"))
    )
    (net (code "180") (name "unconnected-(U7-ALERT-Pad3)") (class "Default")
      (node (ref "U7") (pin "3") (pinfunction "ALERT_3") (pintype "passive+no_connect"))
    )
    (net (code "181") (name "unconnected-(U8-KEY--Pad15)") (class "Default")
      (node (ref "U8") (pin "15") (pinfunction "KEY-_15") (pintype "passive"))
    )
    (net (code "182") (name "unconnected-(U8-LED-Pad16)") (class "Default")
      (node (ref "U8") (pin "16") (pinfunction "LED_16") (pintype "passive"))
    )
    (net (code "183") (name "unconnected-(U8-LEDCON-Pad14)") (class "Default")
      (node (ref "U8") (pin "14") (pinfunction "LEDCON_14") (pintype "passive"))
    )
    (net (code "184") (name "unconnected-(U8-NC-Pad3)") (class "Default")
      (node (ref "U8") (pin "3") (pinfunction "NC_3") (pintype "passive"))
    )
    (net (code "185") (name "unconnected-(U8-NC-Pad4)") (class "Default")
      (node (ref "U8") (pin "4") (pinfunction "NC_4") (pintype "passive"))
    )
    (net (code "186") (name "unconnected-(U8-NC-Pad5)") (class "Default")
      (node (ref "U8") (pin "5") (pinfunction "NC_5") (pintype "passive"))
    )
    (net (code "187") (name "unconnected-(U8-NC-Pad6)") (class "Default")
      (node (ref "U8") (pin "6") (pinfunction "NC_6") (pintype "passive"))
    )
    (net (code "188") (name "unconnected-(U8-NC-Pad7)") (class "Default")
      (node (ref "U8") (pin "7") (pinfunction "NC_7") (pintype "passive"))
    )
    (net (code "189") (name "unconnected-(U8-NC-Pad8)") (class "Default")
      (node (ref "U8") (pin "8") (pinfunction "NC_8") (pintype "passive"))
    )
    (net (code "190") (name "unconnected-(U8-NC-Pad9)") (class "Default")
      (node (ref "U8") (pin "9") (pinfunction "NC_9") (pintype "passive"))
    )
    (net (code "191") (name "unconnected-(U8-NC-Pad10)") (class "Default")
      (node (ref "U8") (pin "10") (pinfunction "NC_10") (pintype "passive"))
    )
    (net (code "192") (name "unconnected-(U8-NC-Pad19)") (class "Default")
      (node (ref "U8") (pin "19") (pinfunction "NC_19") (pintype "passive"))
    )
    (net (code "193") (name "unconnected-(U8-NC-Pad20)") (class "Default")
      (node (ref "U8") (pin "20") (pinfunction "NC_20") (pintype "passive"))
    )
    (net (code "194") (name "unconnected-(U8-NC-Pad21)") (class "Default")
      (node (ref "U8") (pin "21") (pinfunction "NC_21") (pintype "passive"))
    )
    (net (code "195") (name "unconnected-(U8-NC-Pad22)") (class "Default")
      (node (ref "U8") (pin "22") (pinfunction "NC_22") (pintype "passive"))
    )
    (net (code "196") (name "unconnected-(U8-NC-Pad23)") (class "Default")
      (node (ref "U8") (pin "23") (pinfunction "NC_23") (pintype "passive"))
    )
    (net (code "197") (name "unconnected-(U8-NC-Pad24)") (class "Default")
      (node (ref "U8") (pin "24") (pinfunction "NC_24") (pintype "passive"))
    )
    (net (code "198") (name "unconnected-(U8-NC-Pad25)") (class "Default")
      (node (ref "U8") (pin "25") (pinfunction "NC_25") (pintype "passive"))
    )
    (net (code "199") (name "unconnected-(U8-NC-Pad26)") (class "Default")
      (node (ref "U8") (pin "26") (pinfunction "NC_26") (pintype "passive"))
    )
    (net (code "200") (name "unconnected-(U8-~{RST}-Pad11)") (class "Default")
      (node (ref "U8") (pin "11") (pinfunction "~{RST}_11") (pintype "passive"))
    )
  )
)
